# v7-flex2811_long.net
KiCad netlist of a schematic drawn in EAGLE
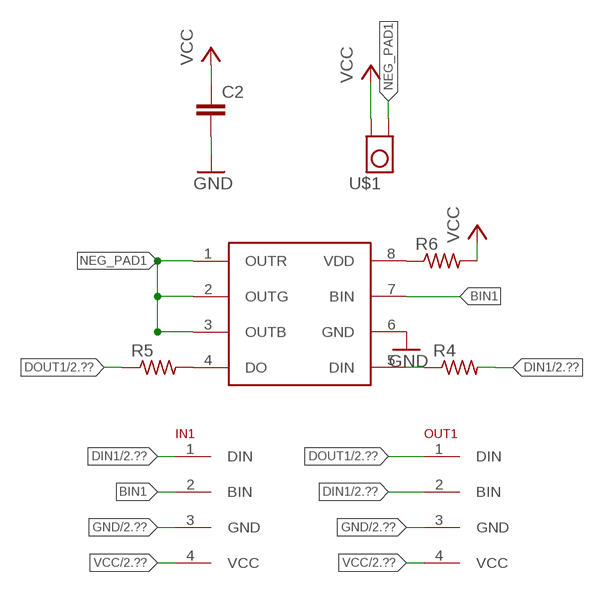
[diagram p0: schematic, sheet 1]
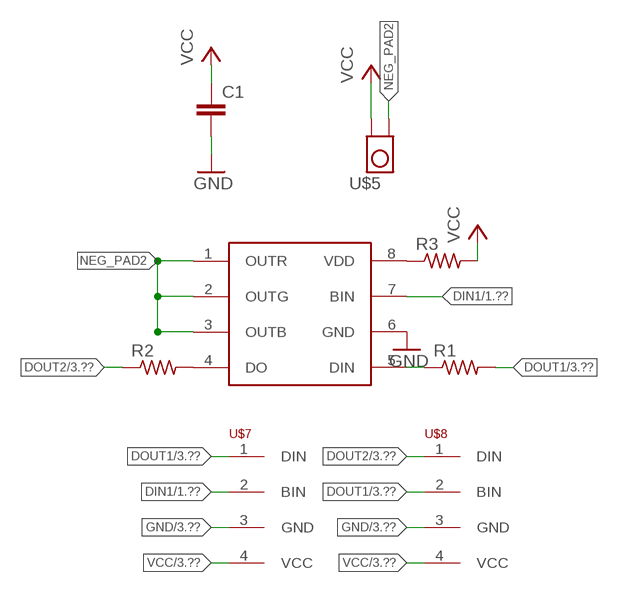
[diagram p1: schematic, sheet 2]
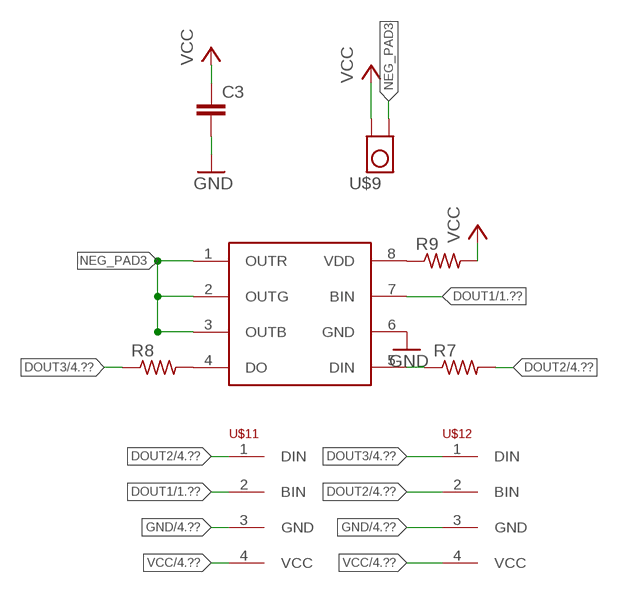
[diagram p2: schematic, sheet 3]
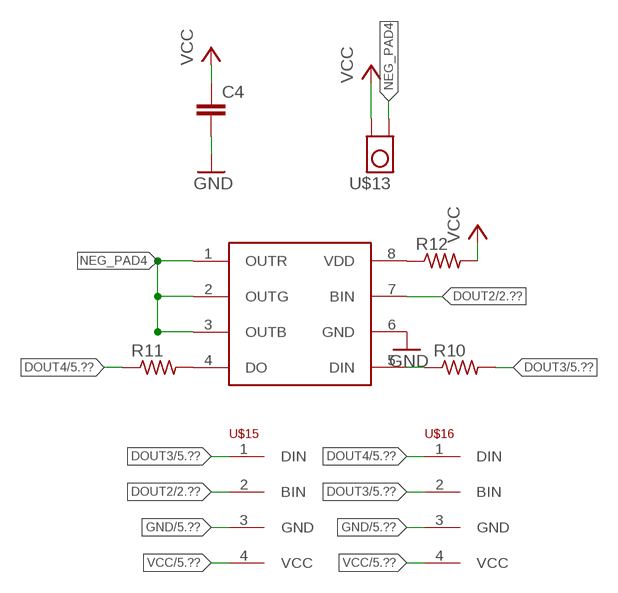
[diagram p3: schematic, sheet 4]
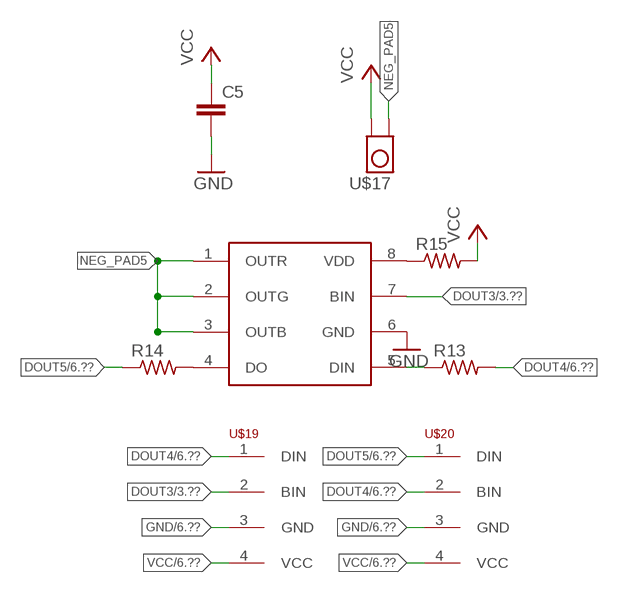
[diagram p4: schematic, sheet 5]
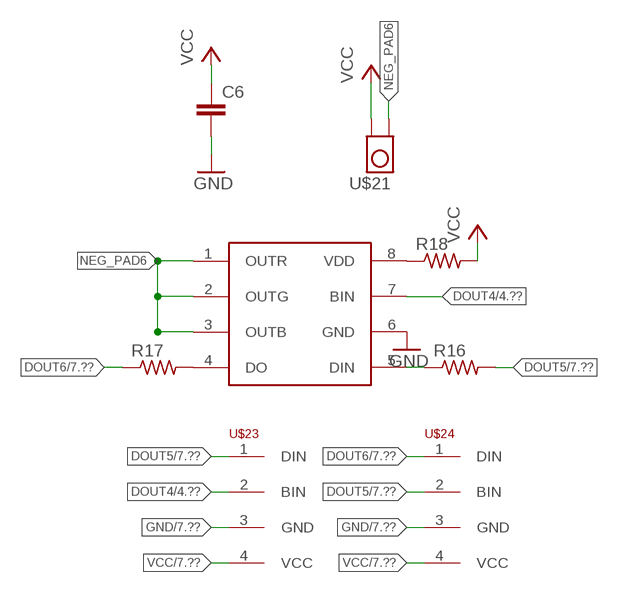
[diagram p5: schematic, sheet 6]
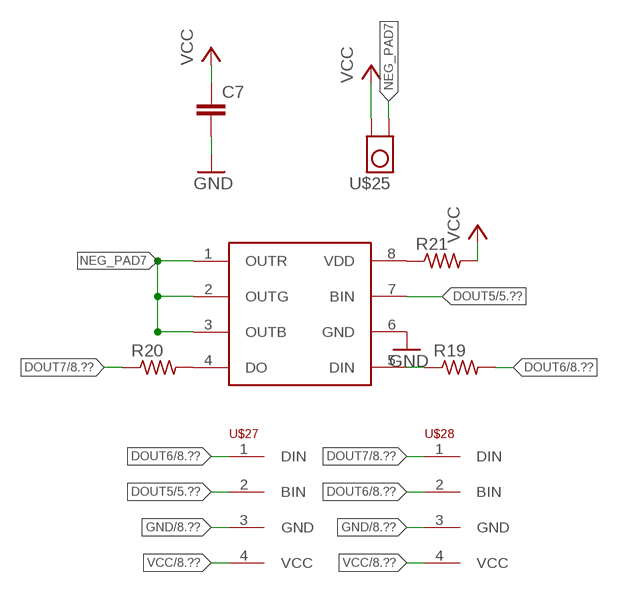
[diagram p6: schematic, sheet 7]
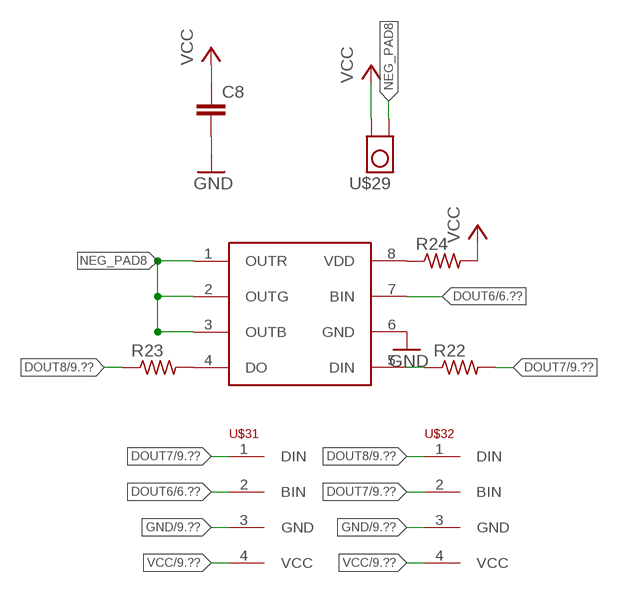
[diagram p7: schematic, sheet 8]
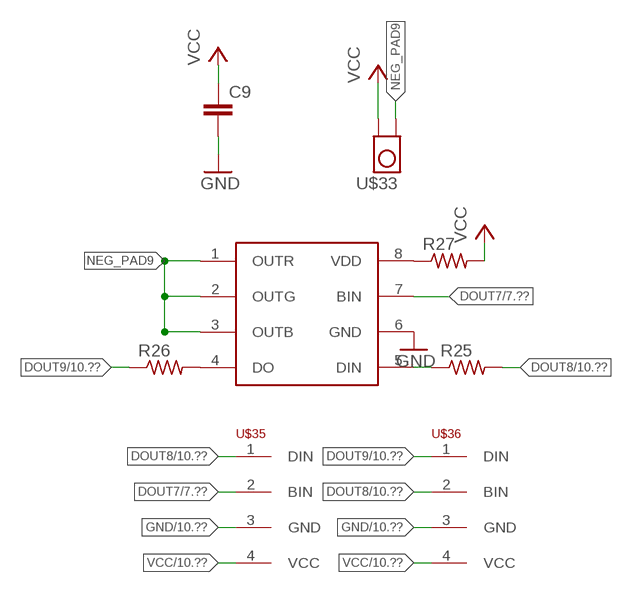
[diagram p8: schematic, sheet 9]
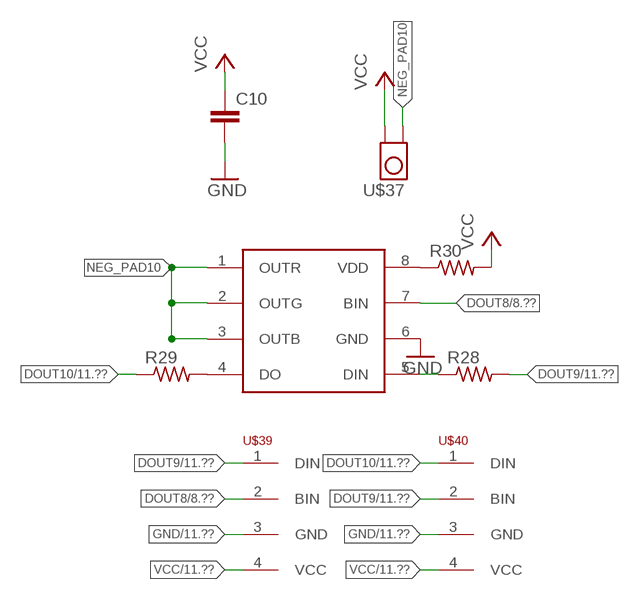
[diagram p9: schematic, sheet 10]
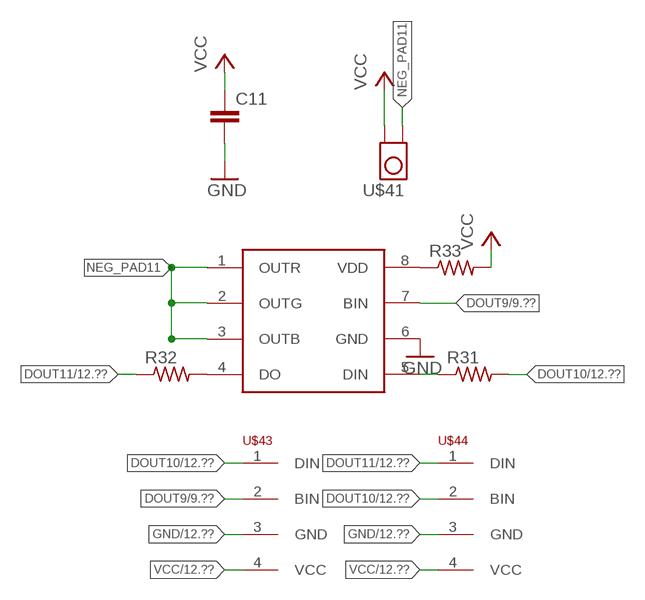
[diagram p10: schematic, sheet 11]
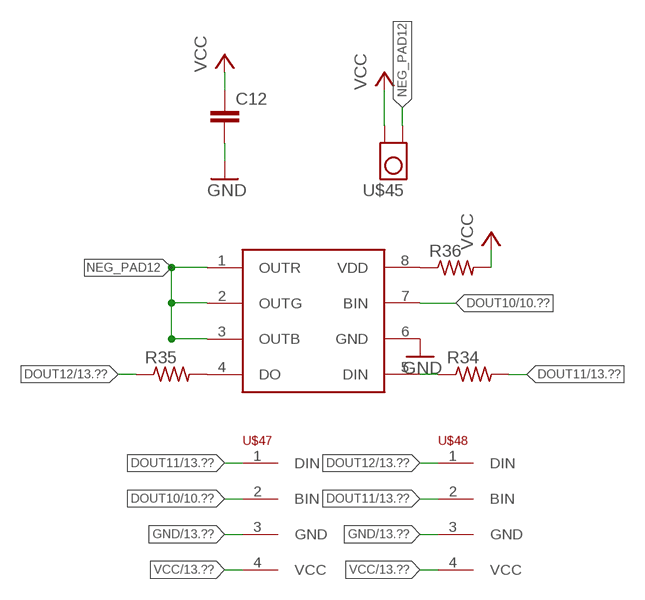
[diagram p11: schematic, sheet 12]
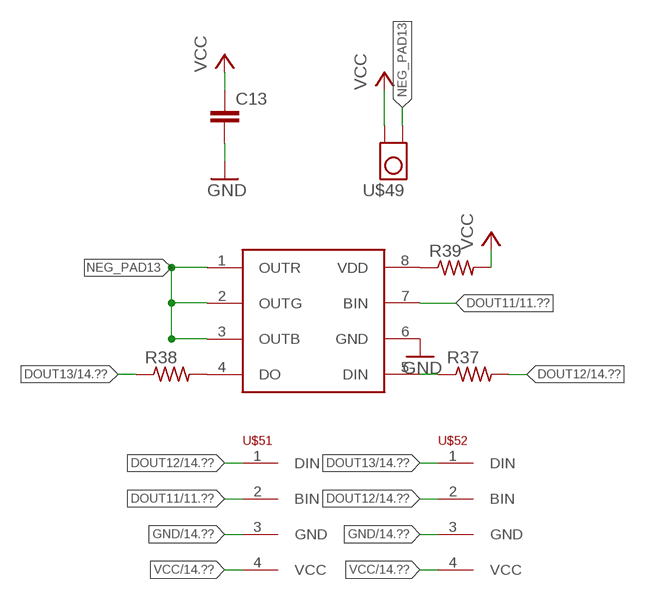
[diagram p12: schematic, sheet 13]
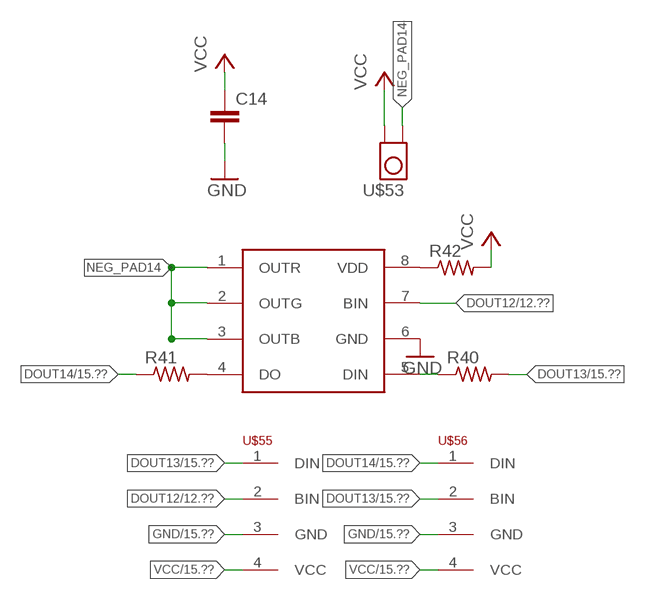
[diagram p13: schematic, sheet 14]
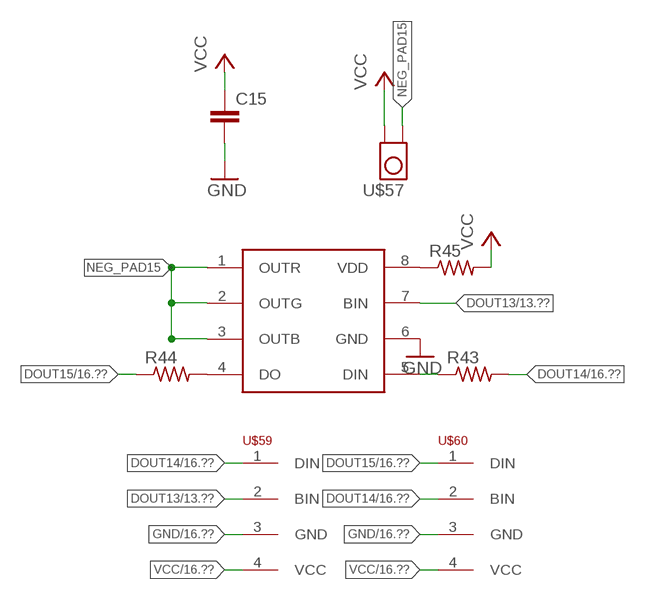
[diagram p14: schematic, sheet 15]
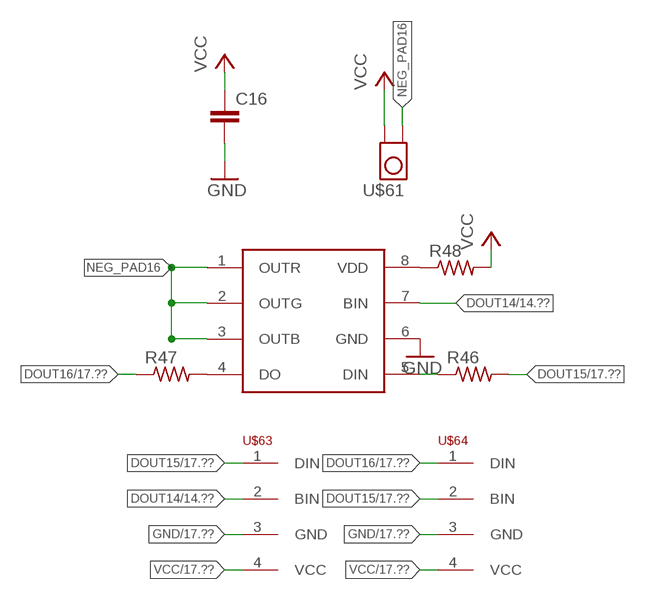
[diagram p15: schematic, sheet 16]
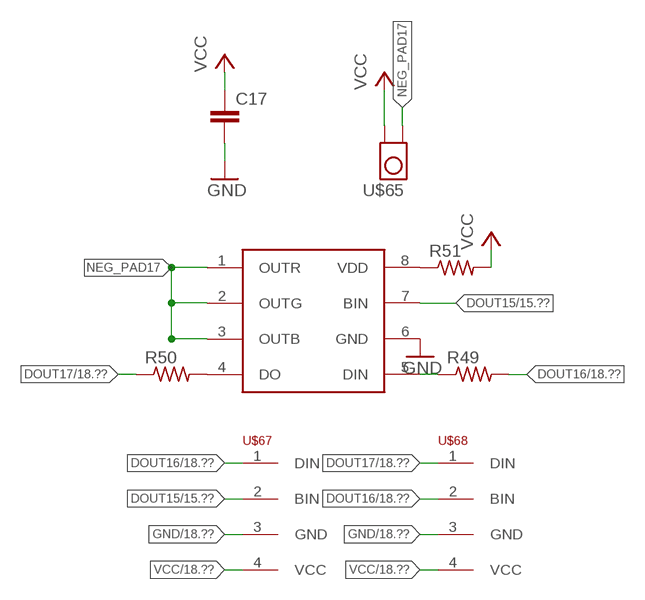
[diagram p16: schematic, sheet 17]
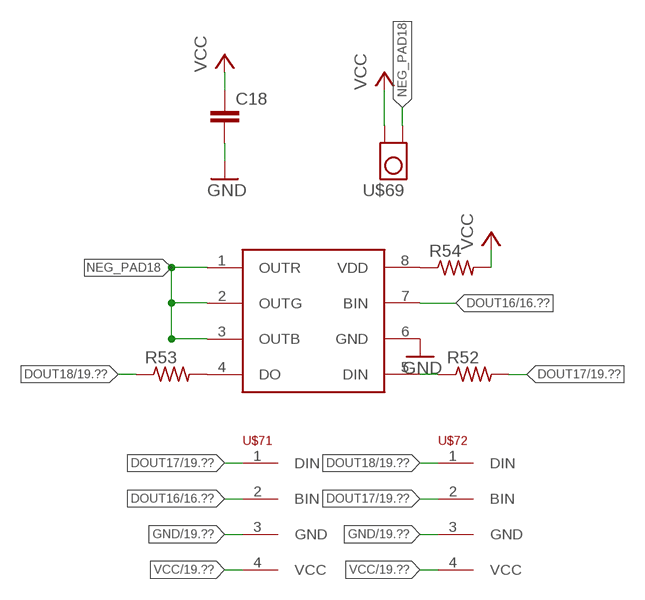
[diagram p17: schematic, sheet 18]
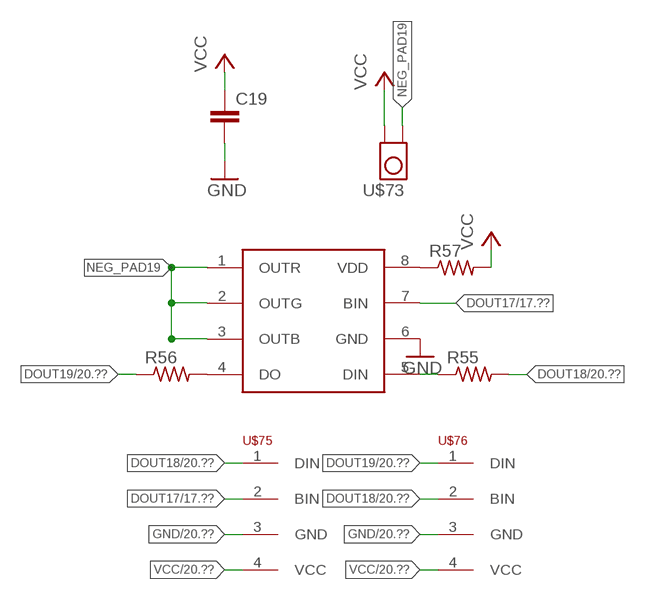
[diagram p18: schematic, sheet 19]
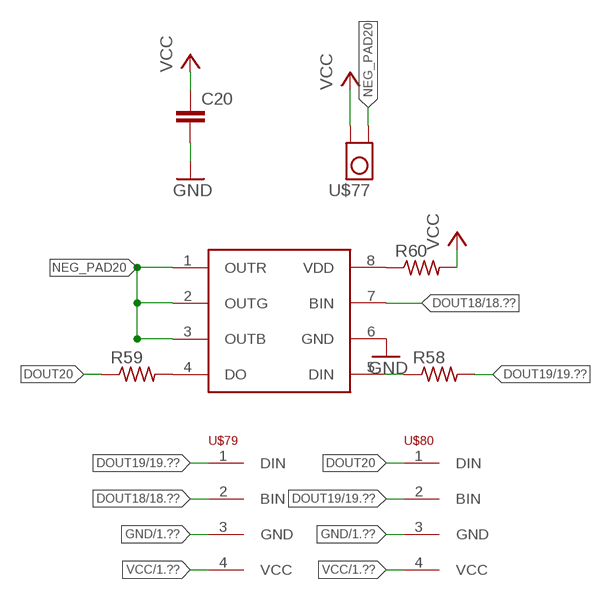
[diagram p19: schematic, sheet 20]

(export (version "E")
  (design (tool "Eeschema 10.0.6"))
  (components
    (comp (ref "C20")
      (value "C-EUC0201")
      (footprint "eagle-import:C0201")
      (libsource (lib "eagle-import") (part "C-EUC0201"))
    )
    (comp (ref "R58")
      (value "R-US_R0201")
      (footprint "eagle-import:R0201")
      (libsource (lib "eagle-import") (part "R-US_R0201"))
    )
    (comp (ref "R59")
      (value "R-US_R0201")
      (footprint "eagle-import:R0201")
      (libsource (lib "eagle-import") (part "R-US_R0201"))
    )
    (comp (ref "R60")
      (value "R-US_R0201")
      (footprint "eagle-import:R0201")
      (libsource (lib "eagle-import") (part "R-US_R0201"))
    )
    (comp (ref "U$77")
      (value "TP_4MM_MED_PAD")
      (footprint "eagle-import:TP_4MM_MED_PAD")
      (libsource (lib "eagle-import") (part "TP_4MM_MED_PAD"))
    )
    (comp (ref "U$78")
      (value "WS2818")
      (footprint "eagle-import:SO08")
      (libsource (lib "eagle-import") (part "adafruit_WS2818"))
    )
    (comp (ref "U$79")
      (value "4PAD")
      (footprint "eagle-import:4PAD")
      (libsource (lib "eagle-import") (part "4PAD"))
    )
    (comp (ref "U$80")
      (value "4PAD")
      (footprint "eagle-import:4PAD")
      (libsource (lib "eagle-import") (part "4PAD"))
    )
    (comp (ref "C16")
      (value "C-EUC0201")
      (footprint "eagle-import:C0201")
      (libsource (lib "eagle-import") (part "C-EUC0201"))
    )
    (comp (ref "R46")
      (value "R-US_R0201")
      (footprint "eagle-import:R0201")
      (libsource (lib "eagle-import") (part "R-US_R0201"))
    )
    (comp (ref "R47")
      (value "R-US_R0201")
      (footprint "eagle-import:R0201")
      (libsource (lib "eagle-import") (part "R-US_R0201"))
    )
    (comp (ref "R48")
      (value "R-US_R0201")
      (footprint "eagle-import:R0201")
      (libsource (lib "eagle-import") (part "R-US_R0201"))
    )
    (comp (ref "U$61")
      (value "TP_4MM_MED_PAD")
      (footprint "eagle-import:TP_4MM_MED_PAD")
      (libsource (lib "eagle-import") (part "TP_4MM_MED_PAD"))
    )
    (comp (ref "U$62")
      (value "WS2818")
      (footprint "eagle-import:SO08")
      (libsource (lib "eagle-import") (part "adafruit_WS2818"))
    )
    (comp (ref "U$63")
      (value "4PAD")
      (footprint "eagle-import:4PAD")
      (libsource (lib "eagle-import") (part "4PAD"))
    )
    (comp (ref "U$64")
      (value "4PAD")
      (footprint "eagle-import:4PAD")
      (libsource (lib "eagle-import") (part "4PAD"))
    )
    (comp (ref "C6")
      (value "C-EUC0201")
      (footprint "eagle-import:C0201")
      (libsource (lib "eagle-import") (part "C-EUC0201"))
    )
    (comp (ref "R16")
      (value "R-US_R0201")
      (footprint "eagle-import:R0201")
      (libsource (lib "eagle-import") (part "R-US_R0201"))
    )
    (comp (ref "R17")
      (value "R-US_R0201")
      (footprint "eagle-import:R0201")
      (libsource (lib "eagle-import") (part "R-US_R0201"))
    )
    (comp (ref "R18")
      (value "R-US_R0201")
      (footprint "eagle-import:R0201")
      (libsource (lib "eagle-import") (part "R-US_R0201"))
    )
    (comp (ref "U$21")
      (value "TP_4MM_MED_PAD")
      (footprint "eagle-import:TP_4MM_MED_PAD")
      (libsource (lib "eagle-import") (part "TP_4MM_MED_PAD"))
    )
    (comp (ref "U$22")
      (value "WS2818")
      (footprint "eagle-import:SO08")
      (libsource (lib "eagle-import") (part "adafruit_WS2818"))
    )
    (comp (ref "U$23")
      (value "4PAD")
      (footprint "eagle-import:4PAD")
      (libsource (lib "eagle-import") (part "4PAD"))
    )
    (comp (ref "U$24")
      (value "4PAD")
      (footprint "eagle-import:4PAD")
      (libsource (lib "eagle-import") (part "4PAD"))
    )
    (comp (ref "C18")
      (value "C-EUC0201")
      (footprint "eagle-import:C0201")
      (libsource (lib "eagle-import") (part "C-EUC0201"))
    )
    (comp (ref "R52")
      (value "R-US_R0201")
      (footprint "eagle-import:R0201")
      (libsource (lib "eagle-import") (part "R-US_R0201"))
    )
    (comp (ref "R53")
      (value "R-US_R0201")
      (footprint "eagle-import:R0201")
      (libsource (lib "eagle-import") (part "R-US_R0201"))
    )
    (comp (ref "R54")
      (value "R-US_R0201")
      (footprint "eagle-import:R0201")
      (libsource (lib "eagle-import") (part "R-US_R0201"))
    )
    (comp (ref "U$69")
      (value "TP_4MM_MED_PAD")
      (footprint "eagle-import:TP_4MM_MED_PAD")
      (libsource (lib "eagle-import") (part "TP_4MM_MED_PAD"))
    )
    (comp (ref "U$70")
      (value "WS2818")
      (footprint "eagle-import:SO08")
      (libsource (lib "eagle-import") (part "adafruit_WS2818"))
    )
    (comp (ref "U$71")
      (value "4PAD")
      (footprint "eagle-import:4PAD")
      (libsource (lib "eagle-import") (part "4PAD"))
    )
    (comp (ref "U$72")
      (value "4PAD")
      (footprint "eagle-import:4PAD")
      (libsource (lib "eagle-import") (part "4PAD"))
    )
    (comp (ref "C12")
      (value "C-EUC0201")
      (footprint "eagle-import:C0201")
      (libsource (lib "eagle-import") (part "C-EUC0201"))
    )
    (comp (ref "R34")
      (value "R-US_R0201")
      (footprint "eagle-import:R0201")
      (libsource (lib "eagle-import") (part "R-US_R0201"))
    )
    (comp (ref "R35")
      (value "R-US_R0201")
      (footprint "eagle-import:R0201")
      (libsource (lib "eagle-import") (part "R-US_R0201"))
    )
    (comp (ref "R36")
      (value "R-US_R0201")
      (footprint "eagle-import:R0201")
      (libsource (lib "eagle-import") (part "R-US_R0201"))
    )
    (comp (ref "U$45")
      (value "TP_4MM_MED_PAD")
      (footprint "eagle-import:TP_4MM_MED_PAD")
      (libsource (lib "eagle-import") (part "TP_4MM_MED_PAD"))
    )
    (comp (ref "U$46")
      (value "WS2818")
      (footprint "eagle-import:SO08")
      (libsource (lib "eagle-import") (part "adafruit_WS2818"))
    )
    (comp (ref "U$47")
      (value "4PAD")
      (footprint "eagle-import:4PAD")
      (libsource (lib "eagle-import") (part "4PAD"))
    )
    (comp (ref "U$48")
      (value "4PAD")
      (footprint "eagle-import:4PAD")
      (libsource (lib "eagle-import") (part "4PAD"))
    )
    (comp (ref "C11")
      (value "C-EUC0201")
      (footprint "eagle-import:C0201")
      (libsource (lib "eagle-import") (part "C-EUC0201"))
    )
    (comp (ref "R31")
      (value "R-US_R0201")
      (footprint "eagle-import:R0201")
      (libsource (lib "eagle-import") (part "R-US_R0201"))
    )
    (comp (ref "R32")
      (value "R-US_R0201")
      (footprint "eagle-import:R0201")
      (libsource (lib "eagle-import") (part "R-US_R0201"))
    )
    (comp (ref "R33")
      (value "R-US_R0201")
      (footprint "eagle-import:R0201")
      (libsource (lib "eagle-import") (part "R-US_R0201"))
    )
    (comp (ref "U$41")
      (value "TP_4MM_MED_PAD")
      (footprint "eagle-import:TP_4MM_MED_PAD")
      (libsource (lib "eagle-import") (part "TP_4MM_MED_PAD"))
    )
    (comp (ref "U$42")
      (value "WS2818")
      (footprint "eagle-import:SO08")
      (libsource (lib "eagle-import") (part "adafruit_WS2818"))
    )
    (comp (ref "U$43")
      (value "4PAD")
      (footprint "eagle-import:4PAD")
      (libsource (lib "eagle-import") (part "4PAD"))
    )
    (comp (ref "U$44")
      (value "4PAD")
      (footprint "eagle-import:4PAD")
      (libsource (lib "eagle-import") (part "4PAD"))
    )
    (comp (ref "C10")
      (value "C-EUC0201")
      (footprint "eagle-import:C0201")
      (libsource (lib "eagle-import") (part "C-EUC0201"))
    )
    (comp (ref "R28")
      (value "R-US_R0201")
      (footprint "eagle-import:R0201")
      (libsource (lib "eagle-import") (part "R-US_R0201"))
    )
    (comp (ref "R29")
      (value "R-US_R0201")
      (footprint "eagle-import:R0201")
      (libsource (lib "eagle-import") (part "R-US_R0201"))
    )
    (comp (ref "R30")
      (value "R-US_R0201")
      (footprint "eagle-import:R0201")
      (libsource (lib "eagle-import") (part "R-US_R0201"))
    )
    (comp (ref "U$37")
      (value "TP_4MM_MED_PAD")
      (footprint "eagle-import:TP_4MM_MED_PAD")
      (libsource (lib "eagle-import") (part "TP_4MM_MED_PAD"))
    )
    (comp (ref "U$38")
      (value "WS2818")
      (footprint "eagle-import:SO08")
      (libsource (lib "eagle-import") (part "adafruit_WS2818"))
    )
    (comp (ref "U$39")
      (value "4PAD")
      (footprint "eagle-import:4PAD")
      (libsource (lib "eagle-import") (part "4PAD"))
    )
    (comp (ref "U$40")
      (value "4PAD")
      (footprint "eagle-import:4PAD")
      (libsource (lib "eagle-import") (part "4PAD"))
    )
    (comp (ref "C7")
      (value "C-EUC0201")
      (footprint "eagle-import:C0201")
      (libsource (lib "eagle-import") (part "C-EUC0201"))
    )
    (comp (ref "R19")
      (value "R-US_R0201")
      (footprint "eagle-import:R0201")
      (libsource (lib "eagle-import") (part "R-US_R0201"))
    )
    (comp (ref "R20")
      (value "R-US_R0201")
      (footprint "eagle-import:R0201")
      (libsource (lib "eagle-import") (part "R-US_R0201"))
    )
    (comp (ref "R21")
      (value "R-US_R0201")
      (footprint "eagle-import:R0201")
      (libsource (lib "eagle-import") (part "R-US_R0201"))
    )
    (comp (ref "U$25")
      (value "TP_4MM_MED_PAD")
      (footprint "eagle-import:TP_4MM_MED_PAD")
      (libsource (lib "eagle-import") (part "TP_4MM_MED_PAD"))
    )
    (comp (ref "U$26")
      (value "WS2818")
      (footprint "eagle-import:SO08")
      (libsource (lib "eagle-import") (part "adafruit_WS2818"))
    )
    (comp (ref "U$27")
      (value "4PAD")
      (footprint "eagle-import:4PAD")
      (libsource (lib "eagle-import") (part "4PAD"))
    )
    (comp (ref "U$28")
      (value "4PAD")
      (footprint "eagle-import:4PAD")
      (libsource (lib "eagle-import") (part "4PAD"))
    )
    (comp (ref "C2")
      (value "C-EUC0201")
      (footprint "eagle-import:C0201")
      (libsource (lib "eagle-import") (part "C-EUC0201"))
    )
    (comp (ref "IN1")
      (value "4PAD")
      (footprint "eagle-import:4PAD")
      (libsource (lib "eagle-import") (part "4PAD"))
    )
    (comp (ref "OUT1")
      (value "4PAD")
      (footprint "eagle-import:4PAD")
      (libsource (lib "eagle-import") (part "4PAD"))
    )
    (comp (ref "R4")
      (value "R-US_R0201")
      (footprint "eagle-import:R0201")
      (libsource (lib "eagle-import") (part "R-US_R0201"))
    )
    (comp (ref "R5")
      (value "R-US_R0201")
      (footprint "eagle-import:R0201")
      (libsource (lib "eagle-import") (part "R-US_R0201"))
    )
    (comp (ref "R6")
      (value "R-US_R0201")
      (footprint "eagle-import:R0201")
      (libsource (lib "eagle-import") (part "R-US_R0201"))
    )
    (comp (ref "U$1")
      (value "TP_4MM_MED_PAD")
      (footprint "eagle-import:TP_4MM_MED_PAD")
      (libsource (lib "eagle-import") (part "TP_4MM_MED_PAD"))
    )
    (comp (ref "U$2")
      (value "WS2818")
      (footprint "eagle-import:SO08")
      (libsource (lib "eagle-import") (part "WS2818"))
    )
    (comp (ref "C4")
      (value "C-EUC0201")
      (footprint "eagle-import:C0201")
      (libsource (lib "eagle-import") (part "C-EUC0201"))
    )
    (comp (ref "R10")
      (value "R-US_R0201")
      (footprint "eagle-import:R0201")
      (libsource (lib "eagle-import") (part "R-US_R0201"))
    )
    (comp (ref "R11")
      (value "R-US_R0201")
      (footprint "eagle-import:R0201")
      (libsource (lib "eagle-import") (part "R-US_R0201"))
    )
    (comp (ref "R12")
      (value "R-US_R0201")
      (footprint "eagle-import:R0201")
      (libsource (lib "eagle-import") (part "R-US_R0201"))
    )
    (comp (ref "U$13")
      (value "TP_4MM_MED_PAD")
      (footprint "eagle-import:TP_4MM_MED_PAD")
      (libsource (lib "eagle-import") (part "TP_4MM_MED_PAD"))
    )
    (comp (ref "U$14")
      (value "WS2818")
      (footprint "eagle-import:SO08")
      (libsource (lib "eagle-import") (part "adafruit_WS2818"))
    )
    (comp (ref "U$15")
      (value "4PAD")
      (footprint "eagle-import:4PAD")
      (libsource (lib "eagle-import") (part "4PAD"))
    )
    (comp (ref "U$16")
      (value "4PAD")
      (footprint "eagle-import:4PAD")
      (libsource (lib "eagle-import") (part "4PAD"))
    )
    (comp (ref "C3")
      (value "C-EUC0201")
      (footprint "eagle-import:C0201")
      (libsource (lib "eagle-import") (part "C-EUC0201"))
    )
    (comp (ref "R7")
      (value "R-US_R0201")
      (footprint "eagle-import:R0201")
      (libsource (lib "eagle-import") (part "R-US_R0201"))
    )
    (comp (ref "R8")
      (value "R-US_R0201")
      (footprint "eagle-import:R0201")
      (libsource (lib "eagle-import") (part "R-US_R0201"))
    )
    (comp (ref "R9")
      (value "R-US_R0201")
      (footprint "eagle-import:R0201")
      (libsource (lib "eagle-import") (part "R-US_R0201"))
    )
    (comp (ref "U$9")
      (value "TP_4MM_MED_PAD")
      (footprint "eagle-import:TP_4MM_MED_PAD")
      (libsource (lib "eagle-import") (part "TP_4MM_MED_PAD"))
    )
    (comp (ref "U$10")
      (value "WS2818")
      (footprint "eagle-import:SO08")
      (libsource (lib "eagle-import") (part "adafruit_WS2818"))
    )
    (comp (ref "U$11")
      (value "4PAD")
      (footprint "eagle-import:4PAD")
      (libsource (lib "eagle-import") (part "4PAD"))
    )
    (comp (ref "U$12")
      (value "4PAD")
      (footprint "eagle-import:4PAD")
      (libsource (lib "eagle-import") (part "4PAD"))
    )
    (comp (ref "C17")
      (value "C-EUC0201")
      (footprint "eagle-import:C0201")
      (libsource (lib "eagle-import") (part "C-EUC0201"))
    )
    (comp (ref "R49")
      (value "R-US_R0201")
      (footprint "eagle-import:R0201")
      (libsource (lib "eagle-import") (part "R-US_R0201"))
    )
    (comp (ref "R50")
      (value "R-US_R0201")
      (footprint "eagle-import:R0201")
      (libsource (lib "eagle-import") (part "R-US_R0201"))
    )
    (comp (ref "R51")
      (value "R-US_R0201")
      (footprint "eagle-import:R0201")
      (libsource (lib "eagle-import") (part "R-US_R0201"))
    )
    (comp (ref "U$65")
      (value "TP_4MM_MED_PAD")
      (footprint "eagle-import:TP_4MM_MED_PAD")
      (libsource (lib "eagle-import") (part "TP_4MM_MED_PAD"))
    )
    (comp (ref "U$66")
      (value "WS2818")
      (footprint "eagle-import:SO08")
      (libsource (lib "eagle-import") (part "adafruit_WS2818"))
    )
    (comp (ref "U$67")
      (value "4PAD")
      (footprint "eagle-import:4PAD")
      (libsource (lib "eagle-import") (part "4PAD"))
    )
    (comp (ref "U$68")
      (value "4PAD")
      (footprint "eagle-import:4PAD")
      (libsource (lib "eagle-import") (part "4PAD"))
    )
    (comp (ref "C5")
      (value "C-EUC0201")
      (footprint "eagle-import:C0201")
      (libsource (lib "eagle-import") (part "C-EUC0201"))
    )
    (comp (ref "R13")
      (value "R-US_R0201")
      (footprint "eagle-import:R0201")
      (libsource (lib "eagle-import") (part "R-US_R0201"))
    )
    (comp (ref "R14")
      (value "R-US_R0201")
      (footprint "eagle-import:R0201")
      (libsource (lib "eagle-import") (part "R-US_R0201"))
    )
    (comp (ref "R15")
      (value "R-US_R0201")
      (footprint "eagle-import:R0201")
      (libsource (lib "eagle-import") (part "R-US_R0201"))
    )
    (comp (ref "U$17")
      (value "TP_4MM_MED_PAD")
      (footprint "eagle-import:TP_4MM_MED_PAD")
      (libsource (lib "eagle-import") (part "TP_4MM_MED_PAD"))
    )
    (comp (ref "U$18")
      (value "WS2818")
      (footprint "eagle-import:SO08")
      (libsource (lib "eagle-import") (part "adafruit_WS2818"))
    )
    (comp (ref "U$19")
      (value "4PAD")
      (footprint "eagle-import:4PAD")
      (libsource (lib "eagle-import") (part "4PAD"))
    )
    (comp (ref "U$20")
      (value "4PAD")
      (footprint "eagle-import:4PAD")
      (libsource (lib "eagle-import") (part "4PAD"))
    )
    (comp (ref "C14")
      (value "C-EUC0201")
      (footprint "eagle-import:C0201")
      (libsource (lib "eagle-import") (part "C-EUC0201"))
    )
    (comp (ref "R40")
      (value "R-US_R0201")
      (footprint "eagle-import:R0201")
      (libsource (lib "eagle-import") (part "R-US_R0201"))
    )
    (comp (ref "R41")
      (value "R-US_R0201")
      (footprint "eagle-import:R0201")
      (libsource (lib "eagle-import") (part "R-US_R0201"))
    )
    (comp (ref "R42")
      (value "R-US_R0201")
      (footprint "eagle-import:R0201")
      (libsource (lib "eagle-import") (part "R-US_R0201"))
    )
    (comp (ref "U$53")
      (value "TP_4MM_MED_PAD")
      (footprint "eagle-import:TP_4MM_MED_PAD")
      (libsource (lib "eagle-import") (part "TP_4MM_MED_PAD"))
    )
    (comp (ref "U$54")
      (value "WS2818")
      (footprint "eagle-import:SO08")
      (libsource (lib "eagle-import") (part "adafruit_WS2818"))
    )
    (comp (ref "U$55")
      (value "4PAD")
      (footprint "eagle-import:4PAD")
      (libsource (lib "eagle-import") (part "4PAD"))
    )
    (comp (ref "U$56")
      (value "4PAD")
      (footprint "eagle-import:4PAD")
      (libsource (lib "eagle-import") (part "4PAD"))
    )
    (comp (ref "C19")
      (value "C-EUC0201")
      (footprint "eagle-import:C0201")
      (libsource (lib "eagle-import") (part "C-EUC0201"))
    )
    (comp (ref "R55")
      (value "R-US_R0201")
      (footprint "eagle-import:R0201")
      (libsource (lib "eagle-import") (part "R-US_R0201"))
    )
    (comp (ref "R56")
      (value "R-US_R0201")
      (footprint "eagle-import:R0201")
      (libsource (lib "eagle-import") (part "R-US_R0201"))
    )
    (comp (ref "R57")
      (value "R-US_R0201")
      (footprint "eagle-import:R0201")
      (libsource (lib "eagle-import") (part "R-US_R0201"))
    )
    (comp (ref "U$73")
      (value "TP_4MM_MED_PAD")
      (footprint "eagle-import:TP_4MM_MED_PAD")
      (libsource (lib "eagle-import") (part "TP_4MM_MED_PAD"))
    )
    (comp (ref "U$74")
      (value "WS2818")
      (footprint "eagle-import:SO08")
      (libsource (lib "eagle-import") (part "adafruit_WS2818"))
    )
    (comp (ref "U$75")
      (value "4PAD")
      (footprint "eagle-import:4PAD")
      (libsource (lib "eagle-import") (part "4PAD"))
    )
    (comp (ref "U$76")
      (value "4PAD")
      (footprint "eagle-import:4PAD")
      (libsource (lib "eagle-import") (part "4PAD"))
    )
    (comp (ref "C15")
      (value "C-EUC0201")
      (footprint "eagle-import:C0201")
      (libsource (lib "eagle-import") (part "C-EUC0201"))
    )
    (comp (ref "R43")
      (value "R-US_R0201")
      (footprint "eagle-import:R0201")
      (libsource (lib "eagle-import") (part "R-US_R0201"))
    )
    (comp (ref "R44")
      (value "R-US_R0201")
      (footprint "eagle-import:R0201")
      (libsource (lib "eagle-import") (part "R-US_R0201"))
    )
    (comp (ref "R45")
      (value "R-US_R0201")
      (footprint "eagle-import:R0201")
      (libsource (lib "eagle-import") (part "R-US_R0201"))
    )
    (comp (ref "U$57")
      (value "TP_4MM_MED_PAD")
      (footprint "eagle-import:TP_4MM_MED_PAD")
      (libsource (lib "eagle-import") (part "TP_4MM_MED_PAD"))
    )
    (comp (ref "U$58")
      (value "WS2818")
      (footprint "eagle-import:SO08")
      (libsource (lib "eagle-import") (part "adafruit_WS2818"))
    )
    (comp (ref "U$59")
      (value "4PAD")
      (footprint "eagle-import:4PAD")
      (libsource (lib "eagle-import") (part "4PAD"))
    )
    (comp (ref "U$60")
      (value "4PAD")
      (footprint "eagle-import:4PAD")
      (libsource (lib "eagle-import") (part "4PAD"))
    )
    (comp (ref "C13")
      (value "C-EUC0201")
      (footprint "eagle-import:C0201")
      (libsource (lib "eagle-import") (part "C-EUC0201"))
    )
    (comp (ref "R37")
      (value "R-US_R0201")
      (footprint "eagle-import:R0201")
      (libsource (lib "eagle-import") (part "R-US_R0201"))
    )
    (comp (ref "R38")
      (value "R-US_R0201")
      (footprint "eagle-import:R0201")
      (libsource (lib "eagle-import") (part "R-US_R0201"))
    )
    (comp (ref "R39")
      (value "R-US_R0201")
      (footprint "eagle-import:R0201")
      (libsource (lib "eagle-import") (part "R-US_R0201"))
    )
    (comp (ref "U$49")
      (value "TP_4MM_MED_PAD")
      (footprint "eagle-import:TP_4MM_MED_PAD")
      (libsource (lib "eagle-import") (part "TP_4MM_MED_PAD"))
    )
    (comp (ref "U$50")
      (value "WS2818")
      (footprint "eagle-import:SO08")
      (libsource (lib "eagle-import") (part "adafruit_WS2818"))
    )
    (comp (ref "U$51")
      (value "4PAD")
      (footprint "eagle-import:4PAD")
      (libsource (lib "eagle-import") (part "4PAD"))
    )
    (comp (ref "U$52")
      (value "4PAD")
      (footprint "eagle-import:4PAD")
      (libsource (lib "eagle-import") (part "4PAD"))
    )
    (comp (ref "C9")
      (value "C-EUC0201")
      (footprint "eagle-import:C0201")
      (libsource (lib "eagle-import") (part "C-EUC0201"))
    )
    (comp (ref "R25")
      (value "R-US_R0201")
      (footprint "eagle-import:R0201")
      (libsource (lib "eagle-import") (part "R-US_R0201"))
    )
    (comp (ref "R26")
      (value "R-US_R0201")
      (footprint "eagle-import:R0201")
      (libsource (lib "eagle-import") (part "R-US_R0201"))
    )
    (comp (ref "R27")
      (value "R-US_R0201")
      (footprint "eagle-import:R0201")
      (libsource (lib "eagle-import") (part "R-US_R0201"))
    )
    (comp (ref "U$33")
      (value "TP_4MM_MED_PAD")
      (footprint "eagle-import:TP_4MM_MED_PAD")
      (libsource (lib "eagle-import") (part "TP_4MM_MED_PAD"))
    )
    (comp (ref "U$34")
      (value "WS2818")
      (footprint "eagle-import:SO08")
      (libsource (lib "eagle-import") (part "adafruit_WS2818"))
    )
    (comp (ref "U$35")
      (value "4PAD")
      (footprint "eagle-import:4PAD")
      (libsource (lib "eagle-import") (part "4PAD"))
    )
    (comp (ref "U$36")
      (value "4PAD")
      (footprint "eagle-import:4PAD")
      (libsource (lib "eagle-import") (part "4PAD"))
    )
    (comp (ref "C1")
      (value "C-EUC0201")
      (footprint "eagle-import:C0201")
      (libsource (lib "eagle-import") (part "C-EUC0201"))
    )
    (comp (ref "R1")
      (value "R-US_R0201")
      (footprint "eagle-import:R0201")
      (libsource (lib "eagle-import") (part "R-US_R0201"))
    )
    (comp (ref "R2")
      (value "R-US_R0201")
      (footprint "eagle-import:R0201")
      (libsource (lib "eagle-import") (part "R-US_R0201"))
    )
    (comp (ref "R3")
      (value "R-US_R0201")
      (footprint "eagle-import:R0201")
      (libsource (lib "eagle-import") (part "R-US_R0201"))
    )
    (comp (ref "U$5")
      (value "TP_4MM_MED_PAD")
      (footprint "eagle-import:TP_4MM_MED_PAD")
      (libsource (lib "eagle-import") (part "TP_4MM_MED_PAD"))
    )
    (comp (ref "U$6")
      (value "WS2818")
      (footprint "eagle-import:SO08")
      (libsource (lib "eagle-import") (part "adafruit_WS2818"))
    )
    (comp (ref "U$7")
      (value "4PAD")
      (footprint "eagle-import:4PAD")
      (libsource (lib "eagle-import") (part "4PAD"))
    )
    (comp (ref "U$8")
      (value "4PAD")
      (footprint "eagle-import:4PAD")
      (libsource (lib "eagle-import") (part "4PAD"))
    )
    (comp (ref "C8")
      (value "C-EUC0201")
      (footprint "eagle-import:C0201")
      (libsource (lib "eagle-import") (part "C-EUC0201"))
    )
    (comp (ref "R22")
      (value "R-US_R0201")
      (footprint "eagle-import:R0201")
      (libsource (lib "eagle-import") (part "R-US_R0201"))
    )
    (comp (ref "R23")
      (value "R-US_R0201")
      (footprint "eagle-import:R0201")
      (libsource (lib "eagle-import") (part "R-US_R0201"))
    )
    (comp (ref "R24")
      (value "R-US_R0201")
      (footprint "eagle-import:R0201")
      (libsource (lib "eagle-import") (part "R-US_R0201"))
    )
    (comp (ref "U$29")
      (value "TP_4MM_MED_PAD")
      (footprint "eagle-import:TP_4MM_MED_PAD")
      (libsource (lib "eagle-import") (part "TP_4MM_MED_PAD"))
    )
    (comp (ref "U$30")
      (value "WS2818")
      (footprint "eagle-import:SO08")
      (libsource (lib "eagle-import") (part "adafruit_WS2818"))
    )
    (comp (ref "U$31")
      (value "4PAD")
      (footprint "eagle-import:4PAD")
      (libsource (lib "eagle-import") (part "4PAD"))
    )
    (comp (ref "U$32")
      (value "4PAD")
      (footprint "eagle-import:4PAD")
      (libsource (lib "eagle-import") (part "4PAD"))
    )
  )
  (nets
    (net (code "1") (name "BIN1") (class "Default")
      (node (ref "IN1") (pin "2") (pinfunction "BIN_2") (pintype "bidirectional"))
      (node (ref "U$2") (pin "7") (pinfunction "BIN_7") (pintype "bidirectional"))
    )
    (net (code "2") (name "DIN1") (class "Default")
      (node (ref "IN1") (pin "1") (pinfunction "DIN_1") (pintype "bidirectional"))
      (node (ref "OUT1") (pin "2") (pinfunction "BIN_2") (pintype "bidirectional"))
      (node (ref "R4") (pin "2") (pinfunction "2_2") (pintype "passive"))
      (node (ref "U$6") (pin "7") (pinfunction "BIN_7") (pintype "bidirectional"))
      (node (ref "U$7") (pin "2") (pinfunction "BIN_2") (pintype "bidirectional"))
    )
    (net (code "3") (name "DOUT1") (class "Default")
      (node (ref "OUT1") (pin "1") (pinfunction "DIN_1") (pintype "bidirectional"))
      (node (ref "R1") (pin "2") (pinfunction "2_2") (pintype "passive"))
      (node (ref "R5") (pin "1") (pinfunction "1_1") (pintype "passive"))
      (node (ref "U$10") (pin "7") (pinfunction "BIN_7") (pintype "bidirectional"))
      (node (ref "U$11") (pin "2") (pinfunction "BIN_2") (pintype "bidirectional"))
      (node (ref "U$7") (pin "1") (pinfunction "DIN_1") (pintype "bidirectional"))
      (node (ref "U$8") (pin "2") (pinfunction "BIN_2") (pintype "bidirectional"))
    )
    (net (code "4") (name "DOUT2") (class "Default")
      (node (ref "R2") (pin "1") (pinfunction "1_1") (pintype "passive"))
      (node (ref "R7") (pin "2") (pinfunction "2_2") (pintype "passive"))
      (node (ref "U$11") (pin "1") (pinfunction "DIN_1") (pintype "bidirectional"))
      (node (ref "U$12") (pin "2") (pinfunction "BIN_2") (pintype "bidirectional"))
      (node (ref "U$14") (pin "7") (pinfunction "BIN_7") (pintype "bidirectional"))
      (node (ref "U$15") (pin "2") (pinfunction "BIN_2") (pintype "bidirectional"))
      (node (ref "U$8") (pin "1") (pinfunction "DIN_1") (pintype "bidirectional"))
    )
    (net (code "5") (name "DOUT3") (class "Default")
      (node (ref "R10") (pin "2") (pinfunction "2_2") (pintype "passive"))
      (node (ref "R8") (pin "1") (pinfunction "1_1") (pintype "passive"))
      (node (ref "U$12") (pin "1") (pinfunction "DIN_1") (pintype "bidirectional"))
      (node (ref "U$15") (pin "1") (pinfunction "DIN_1") (pintype "bidirectional"))
      (node (ref "U$16") (pin "2") (pinfunction "BIN_2") (pintype "bidirectional"))
      (node (ref "U$18") (pin "7") (pinfunction "BIN_7") (pintype "bidirectional"))
      (node (ref "U$19") (pin "2") (pinfunction "BIN_2") (pintype "bidirectional"))
    )
    (net (code "6") (name "DOUT4") (class "Default")
      (node (ref "R11") (pin "1") (pinfunction "1_1") (pintype "passive"))
      (node (ref "R13") (pin "2") (pinfunction "2_2") (pintype "passive"))
      (node (ref "U$16") (pin "1") (pinfunction "DIN_1") (pintype "bidirectional"))
      (node (ref "U$19") (pin "1") (pinfunction "DIN_1") (pintype "bidirectional"))
      (node (ref "U$20") (pin "2") (pinfunction "BIN_2") (pintype "bidirectional"))
      (node (ref "U$22") (pin "7") (pinfunction "BIN_7") (pintype "bidirectional"))
      (node (ref "U$23") (pin "2") (pinfunction "BIN_2") (pintype "bidirectional"))
    )
    (net (code "7") (name "DOUT5") (class "Default")
      (node (ref "R14") (pin "1") (pinfunction "1_1") (pintype "passive"))
      (node (ref "R16") (pin "2") (pinfunction "2_2") (pintype "passive"))
      (node (ref "U$20") (pin "1") (pinfunction "DIN_1") (pintype "bidirectional"))
      (node (ref "U$23") (pin "1") (pinfunction "DIN_1") (pintype "bidirectional"))
      (node (ref "U$24") (pin "2") (pinfunction "BIN_2") (pintype "bidirectional"))
      (node (ref "U$26") (pin "7") (pinfunction "BIN_7") (pintype "bidirectional"))
      (node (ref "U$27") (pin "2") (pinfunction "BIN_2") (pintype "bidirectional"))
    )
    (net (code "8") (name "DOUT6") (class "Default")
      (node (ref "R17") (pin "1") (pinfunction "1_1") (pintype "passive"))
      (node (ref "R19") (pin "2") (pinfunction "2_2") (pintype "passive"))
      (node (ref "U$24") (pin "1") (pinfunction "DIN_1") (pintype "bidirectional"))
      (node (ref "U$27") (pin "1") (pinfunction "DIN_1") (pintype "bidirectional"))
      (node (ref "U$28") (pin "2") (pinfunction "BIN_2") (pintype "bidirectional"))
      (node (ref "U$30") (pin "7") (pinfunction "BIN_7") (pintype "bidirectional"))
      (node (ref "U$31") (pin "2") (pinfunction "BIN_2") (pintype "bidirectional"))
    )
    (net (code "9") (name "DOUT7") (class "Default")
      (node (ref "R20") (pin "1") (pinfunction "1_1") (pintype "passive"))
      (node (ref "R22") (pin "2") (pinfunction "2_2") (pintype "passive"))
      (node (ref "U$28") (pin "1") (pinfunction "DIN_1") (pintype "bidirectional"))
      (node (ref "U$31") (pin "1") (pinfunction "DIN_1") (pintype "bidirectional"))
      (node (ref "U$32") (pin "2") (pinfunction "BIN_2") (pintype "bidirectional"))
      (node (ref "U$34") (pin "7") (pinfunction "BIN_7") (pintype "bidirectional"))
      (node (ref "U$35") (pin "2") (pinfunction "BIN_2") (pintype "bidirectional"))
    )
    (net (code "10") (name "DOUT8") (class "Default")
      (node (ref "R23") (pin "1") (pinfunction "1_1") (pintype "passive"))
      (node (ref "R25") (pin "2") (pinfunction "2_2") (pintype "passive"))
      (node (ref "U$32") (pin "1") (pinfunction "DIN_1") (pintype "bidirectional"))
      (node (ref "U$35") (pin "1") (pinfunction "DIN_1") (pintype "bidirectional"))
      (node (ref "U$36") (pin "2") (pinfunction "BIN_2") (pintype "bidirectional"))
      (node (ref "U$38") (pin "7") (pinfunction "BIN_7") (pintype "bidirectional"))
      (node (ref "U$39") (pin "2") (pinfunction "BIN_2") (pintype "bidirectional"))
    )
    (net (code "11") (name "DOUT9") (class "Default")
      (node (ref "R26") (pin "1") (pinfunction "1_1") (pintype "passive"))
      (node (ref "R28") (pin "2") (pinfunction "2_2") (pintype "passive"))
      (node (ref "U$36") (pin "1") (pinfunction "DIN_1") (pintype "bidirectional"))
      (node (ref "U$39") (pin "1") (pinfunction "DIN_1") (pintype "bidirectional"))
      (node (ref "U$40") (pin "2") (pinfunction "BIN_2") (pintype "bidirectional"))
      (node (ref "U$42") (pin "7") (pinfunction "BIN_7") (pintype "bidirectional"))
      (node (ref "U$43") (pin "2") (pinfunction "BIN_2") (pintype "bidirectional"))
    )
    (net (code "12") (name "DOUT10") (class "Default")
      (node (ref "R29") (pin "1") (pinfunction "1_1") (pintype "passive"))
      (node (ref "R31") (pin "2") (pinfunction "2_2") (pintype "passive"))
      (node (ref "U$40") (pin "1") (pinfunction "DIN_1") (pintype "bidirectional"))
      (node (ref "U$43") (pin "1") (pinfunction "DIN_1") (pintype "bidirectional"))
      (node (ref "U$44") (pin "2") (pinfunction "BIN_2") (pintype "bidirectional"))
      (node (ref "U$46") (pin "7") (pinfunction "BIN_7") (pintype "bidirectional"))
      (node (ref "U$47") (pin "2") (pinfunction "BIN_2") (pintype "bidirectional"))
    )
    (net (code "13") (name "DOUT11") (class "Default")
      (node (ref "R32") (pin "1") (pinfunction "1_1") (pintype "passive"))
      (node (ref "R34") (pin "2") (pinfunction "2_2") (pintype "passive"))
      (node (ref "U$44") (pin "1") (pinfunction "DIN_1") (pintype "bidirectional"))
      (node (ref "U$47") (pin "1") (pinfunction "DIN_1") (pintype "bidirectional"))
      (node (ref "U$48") (pin "2") (pinfunction "BIN_2") (pintype "bidirectional"))
      (node (ref "U$50") (pin "7") (pinfunction "BIN_7") (pintype "bidirectional"))
      (node (ref "U$51") (pin "2") (pinfunction "BIN_2") (pintype "bidirectional"))
    )
    (net (code "14") (name "DOUT12") (class "Default")
      (node (ref "R35") (pin "1") (pinfunction "1_1") (pintype "passive"))
      (node (ref "R37") (pin "2") (pinfunction "2_2") (pintype "passive"))
      (node (ref "U$48") (pin "1") (pinfunction "DIN_1") (pintype "bidirectional"))
      (node (ref "U$51") (pin "1") (pinfunction "DIN_1") (pintype "bidirectional"))
      (node (ref "U$52") (pin "2") (pinfunction "BIN_2") (pintype "bidirectional"))
      (node (ref "U$54") (pin "7") (pinfunction "BIN_7") (pintype "bidirectional"))
      (node (ref "U$55") (pin "2") (pinfunction "BIN_2") (pintype "bidirectional"))
    )
    (net (code "15") (name "DOUT13") (class "Default")
      (node (ref "R38") (pin "1") (pinfunction "1_1") (pintype "passive"))
      (node (ref "R40") (pin "2") (pinfunction "2_2") (pintype "passive"))
      (node (ref "U$52") (pin "1") (pinfunction "DIN_1") (pintype "bidirectional"))
      (node (ref "U$55") (pin "1") (pinfunction "DIN_1") (pintype "bidirectional"))
      (node (ref "U$56") (pin "2") (pinfunction "BIN_2") (pintype "bidirectional"))
      (node (ref "U$58") (pin "7") (pinfunction "BIN_7") (pintype "bidirectional"))
      (node (ref "U$59") (pin "2") (pinfunction "BIN_2") (pintype "bidirectional"))
    )
    (net (code "16") (name "DOUT14") (class "Default")
      (node (ref "R41") (pin "1") (pinfunction "1_1") (pintype "passive"))
      (node (ref "R43") (pin "2") (pinfunction "2_2") (pintype "passive"))
      (node (ref "U$56") (pin "1") (pinfunction "DIN_1") (pintype "bidirectional"))
      (node (ref "U$59") (pin "1") (pinfunction "DIN_1") (pintype "bidirectional"))
      (node (ref "U$60") (pin "2") (pinfunction "BIN_2") (pintype "bidirectional"))
      (node (ref "U$62") (pin "7") (pinfunction "BIN_7") (pintype "bidirectional"))
      (node (ref "U$63") (pin "2") (pinfunction "BIN_2") (pintype "bidirectional"))
    )
    (net (code "17") (name "DOUT15") (class "Default")
      (node (ref "R44") (pin "1") (pinfunction "1_1") (pintype "passive"))
      (node (ref "R46") (pin "2") (pinfunction "2_2") (pintype "passive"))
      (node (ref "U$60") (pin "1") (pinfunction "DIN_1") (pintype "bidirectional"))
      (node (ref "U$63") (pin "1") (pinfunction "DIN_1") (pintype "bidirectional"))
      (node (ref "U$64") (pin "2") (pinfunction "BIN_2") (pintype "bidirectional"))
      (node (ref "U$66") (pin "7") (pinfunction "BIN_7") (pintype "bidirectional"))
      (node (ref "U$67") (pin "2") (pinfunction "BIN_2") (pintype "bidirectional"))
    )
    (net (code "18") (name "DOUT16") (class "Default")
      (node (ref "R47") (pin "1") (pinfunction "1_1") (pintype "passive"))
      (node (ref "R49") (pin "2") (pinfunction "2_2") (pintype "passive"))
      (node (ref "U$64") (pin "1") (pinfunction "DIN_1") (pintype "bidirectional"))
      (node (ref "U$67") (pin "1") (pinfunction "DIN_1") (pintype "bidirectional"))
      (node (ref "U$68") (pin "2") (pinfunction "BIN_2") (pintype "bidirectional"))
      (node (ref "U$70") (pin "7") (pinfunction "BIN_7") (pintype "bidirectional"))
      (node (ref "U$71") (pin "2") (pinfunction "BIN_2") (pintype "bidirectional"))
    )
    (net (code "19") (name "DOUT17") (class "Default")
      (node (ref "R50") (pin "1") (pinfunction "1_1") (pintype "passive"))
      (node (ref "R52") (pin "2") (pinfunction "2_2") (pintype "passive"))
      (node (ref "U$68") (pin "1") (pinfunction "DIN_1") (pintype "bidirectional"))
      (node (ref "U$71") (pin "1") (pinfunction "DIN_1") (pintype "bidirectional"))
      (node (ref "U$72") (pin "2") (pinfunction "BIN_2") (pintype "bidirectional"))
      (node (ref "U$74") (pin "7") (pinfunction "BIN_7") (pintype "bidirectional"))
      (node (ref "U$75") (pin "2") (pinfunction "BIN_2") (pintype "bidirectional"))
    )
    (net (code "20") (name "DOUT18") (class "Default")
      (node (ref "R53") (pin "1") (pinfunction "1_1") (pintype "passive"))
      (node (ref "R55") (pin "2") (pinfunction "2_2") (pintype "passive"))
      (node (ref "U$72") (pin "1") (pinfunction "DIN_1") (pintype "bidirectional"))
      (node (ref "U$75") (pin "1") (pinfunction "DIN_1") (pintype "bidirectional"))
      (node (ref "U$76") (pin "2") (pinfunction "BIN_2") (pintype "bidirectional"))
      (node (ref "U$78") (pin "7") (pinfunction "BIN_7") (pintype "bidirectional"))
      (node (ref "U$79") (pin "2") (pinfunction "BIN_2") (pintype "bidirectional"))
    )
    (net (code "21") (name "DOUT19") (class "Default")
      (node (ref "R56") (pin "1") (pinfunction "1_1") (pintype "passive"))
      (node (ref "R58") (pin "2") (pinfunction "2_2") (pintype "passive"))
      (node (ref "U$76") (pin "1") (pinfunction "DIN_1") (pintype "bidirectional"))
      (node (ref "U$79") (pin "1") (pinfunction "DIN_1") (pintype "bidirectional"))
      (node (ref "U$80") (pin "2") (pinfunction "BIN_2") (pintype "bidirectional"))
    )
    (net (code "22") (name "DOUT20") (class "Default")
      (node (ref "R59") (pin "1") (pinfunction "1_1") (pintype "passive"))
      (node (ref "U$80") (pin "1") (pinfunction "DIN_1") (pintype "bidirectional"))
    )
    (net (code "23") (name "GND") (class "Default")
      (node (ref "C1") (pin "2") (pinfunction "2_2") (pintype "passive"))
      (node (ref "C10") (pin "2") (pinfunction "2_2") (pintype "passive"))
      (node (ref "C11") (pin "2") (pinfunction "2_2") (pintype "passive"))
      (node (ref "C12") (pin "2") (pinfunction "2_2") (pintype "passive"))
      (node (ref "C13") (pin "2") (pinfunction "2_2") (pintype "passive"))
      (node (ref "C14") (pin "2") (pinfunction "2_2") (pintype "passive"))
      (node (ref "C15") (pin "2") (pinfunction "2_2") (pintype "passive"))
      (node (ref "C16") (pin "2") (pinfunction "2_2") (pintype "passive"))
      (node (ref "C17") (pin "2") (pinfunction "2_2") (pintype "passive"))
      (node (ref "C18") (pin "2") (pinfunction "2_2") (pintype "passive"))
      (node (ref "C19") (pin "2") (pinfunction "2_2") (pintype "passive"))
      (node (ref "C2") (pin "2") (pinfunction "2_2") (pintype "passive"))
      (node (ref "C20") (pin "2") (pinfunction "2_2") (pintype "passive"))
      (node (ref "C3") (pin "2") (pinfunction "2_2") (pintype "passive"))
      (node (ref "C4") (pin "2") (pinfunction "2_2") (pintype "passive"))
      (node (ref "C5") (pin "2") (pinfunction "2_2") (pintype "passive"))
      (node (ref "C6") (pin "2") (pinfunction "2_2") (pintype "passive"))
      (node (ref "C7") (pin "2") (pinfunction "2_2") (pintype "passive"))
      (node (ref "C8") (pin "2") (pinfunction "2_2") (pintype "passive"))
      (node (ref "C9") (pin "2") (pinfunction "2_2") (pintype "passive"))
      (node (ref "IN1") (pin "3") (pinfunction "GND_3") (pintype "bidirectional"))
      (node (ref "OUT1") (pin "3") (pinfunction "GND_3") (pintype "bidirectional"))
      (node (ref "U$10") (pin "6") (pinfunction "GND_6") (pintype "bidirectional"))
      (node (ref "U$11") (pin "3") (pinfunction "GND_3") (pintype "bidirectional"))
      (node (ref "U$12") (pin "3") (pinfunction "GND_3") (pintype "bidirectional"))
      (node (ref "U$14") (pin "6") (pinfunction "GND_6") (pintype "bidirectional"))
      (node (ref "U$15") (pin "3") (pinfunction "GND_3") (pintype "bidirectional"))
      (node (ref "U$16") (pin "3") (pinfunction "GND_3") (pintype "bidirectional"))
      (node (ref "U$18") (pin "6") (pinfunction "GND_6") (pintype "bidirectional"))
      (node (ref "U$19") (pin "3") (pinfunction "GND_3") (pintype "bidirectional"))
      (node (ref "U$2") (pin "6") (pinfunction "GND_6") (pintype "bidirectional"))
      (node (ref "U$20") (pin "3") (pinfunction "GND_3") (pintype "bidirectional"))
      (node (ref "U$22") (pin "6") (pinfunction "GND_6") (pintype "bidirectional"))
      (node (ref "U$23") (pin "3") (pinfunction "GND_3") (pintype "bidirectional"))
      (node (ref "U$24") (pin "3") (pinfunction "GND_3") (pintype "bidirectional"))
      (node (ref "U$26") (pin "6") (pinfunction "GND_6") (pintype "bidirectional"))
      (node (ref "U$27") (pin "3") (pinfunction "GND_3") (pintype "bidirectional"))
      (node (ref "U$28") (pin "3") (pinfunction "GND_3") (pintype "bidirectional"))
      (node (ref "U$30") (pin "6") (pinfunction "GND_6") (pintype "bidirectional"))
      (node (ref "U$31") (pin "3") (pinfunction "GND_3") (pintype "bidirectional"))
      (node (ref "U$32") (pin "3") (pinfunction "GND_3") (pintype "bidirectional"))
      (node (ref "U$34") (pin "6") (pinfunction "GND_6") (pintype "bidirectional"))
      (node (ref "U$35") (pin "3") (pinfunction "GND_3") (pintype "bidirectional"))
      (node (ref "U$36") (pin "3") (pinfunction "GND_3") (pintype "bidirectional"))
      (node (ref "U$38") (pin "6") (pinfunction "GND_6") (pintype "bidirectional"))
      (node (ref "U$39") (pin "3") (pinfunction "GND_3") (pintype "bidirectional"))
      (node (ref "U$40") (pin "3") (pinfunction "GND_3") (pintype "bidirectional"))
      (node (ref "U$42") (pin "6") (pinfunction "GND_6") (pintype "bidirectional"))
      (node (ref "U$43") (pin "3") (pinfunction "GND_3") (pintype "bidirectional"))
      (node (ref "U$44") (pin "3") (pinfunction "GND_3") (pintype "bidirectional"))
      (node (ref "U$46") (pin "6") (pinfunction "GND_6") (pintype "bidirectional"))
      (node (ref "U$47") (pin "3") (pinfunction "GND_3") (pintype "bidirectional"))
      (node (ref "U$48") (pin "3") (pinfunction "GND_3") (pintype "bidirectional"))
      (node (ref "U$50") (pin "6") (pinfunction "GND_6") (pintype "bidirectional"))
      (node (ref "U$51") (pin "3") (pinfunction "GND_3") (pintype "bidirectional"))
      (node (ref "U$52") (pin "3") (pinfunction "GND_3") (pintype "bidirectional"))
      (node (ref "U$54") (pin "6") (pinfunction "GND_6") (pintype "bidirectional"))
      (node (ref "U$55") (pin "3") (pinfunction "GND_3") (pintype "bidirectional"))
      (node (ref "U$56") (pin "3") (pinfunction "GND_3") (pintype "bidirectional"))
      (node (ref "U$58") (pin "6") (pinfunction "GND_6") (pintype "bidirectional"))
      (node (ref "U$59") (pin "3") (pinfunction "GND_3") (pintype "bidirectional"))
      (node (ref "U$6") (pin "6") (pinfunction "GND_6") (pintype "bidirectional"))
      (node (ref "U$60") (pin "3") (pinfunction "GND_3") (pintype "bidirectional"))
      (node (ref "U$62") (pin "6") (pinfunction "GND_6") (pintype "bidirectional"))
      (node (ref "U$63") (pin "3") (pinfunction "GND_3") (pintype "bidirectional"))
      (node (ref "U$64") (pin "3") (pinfunction "GND_3") (pintype "bidirectional"))
      (node (ref "U$66") (pin "6") (pinfunction "GND_6") (pintype "bidirectional"))
      (node (ref "U$67") (pin "3") (pinfunction "GND_3") (pintype "bidirectional"))
      (node (ref "U$68") (pin "3") (pinfunction "GND_3") (pintype "bidirectional"))
      (node (ref "U$7") (pin "3") (pinfunction "GND_3") (pintype "bidirectional"))
      (node (ref "U$70") (pin "6") (pinfunction "GND_6") (pintype "bidirectional"))
      (node (ref "U$71") (pin "3") (pinfunction "GND_3") (pintype "bidirectional"))
      (node (ref "U$72") (pin "3") (pinfunction "GND_3") (pintype "bidirectional"))
      (node (ref "U$74") (pin "6") (pinfunction "GND_6") (pintype "bidirectional"))
      (node (ref "U$75") (pin "3") (pinfunction "GND_3") (pintype "bidirectional"))
      (node (ref "U$76") (pin "3") (pinfunction "GND_3") (pintype "bidirectional"))
      (node (ref "U$78") (pin "6") (pinfunction "GND_6") (pintype "bidirectional"))
      (node (ref "U$79") (pin "3") (pinfunction "GND_3") (pintype "bidirectional"))
      (node (ref "U$8") (pin "3") (pinfunction "GND_3") (pintype "bidirectional"))
      (node (ref "U$80") (pin "3") (pinfunction "GND_3") (pintype "bidirectional"))
    )
    (net (code "24") (name "NEG_PAD1") (class "Default")
      (node (ref "U$1") (pin "P$1") (pinfunction "0_P$1") (pintype "bidirectional"))
      (node (ref "U$2") (pin "1") (pinfunction "OUTR_1") (pintype "bidirectional"))
      (node (ref "U$2") (pin "2") (pinfunction "OUTG_2") (pintype "bidirectional"))
      (node (ref "U$2") (pin "3") (pinfunction "OUTB_3") (pintype "bidirectional"))
    )
    (net (code "25") (name "NEG_PAD2") (class "Default")
      (node (ref "U$5") (pin "P$1") (pinfunction "0_P$1") (pintype "bidirectional"))
      (node (ref "U$6") (pin "1") (pinfunction "OUTR_1") (pintype "bidirectional"))
      (node (ref "U$6") (pin "2") (pinfunction "OUTG_2") (pintype "bidirectional"))
      (node (ref "U$6") (pin "3") (pinfunction "OUTB_3") (pintype "bidirectional"))
    )
    (net (code "26") (name "NEG_PAD3") (class "Default")
      (node (ref "U$10") (pin "1") (pinfunction "OUTR_1") (pintype "bidirectional"))
      (node (ref "U$10") (pin "2") (pinfunction "OUTG_2") (pintype "bidirectional"))
      (node (ref "U$10") (pin "3") (pinfunction "OUTB_3") (pintype "bidirectional"))
      (node (ref "U$9") (pin "P$1") (pinfunction "0_P$1") (pintype "bidirectional"))
    )
    (net (code "27") (name "NEG_PAD4") (class "Default")
      (node (ref "U$13") (pin "P$1") (pinfunction "0_P$1") (pintype "bidirectional"))
      (node (ref "U$14") (pin "1") (pinfunction "OUTR_1") (pintype "bidirectional"))
      (node (ref "U$14") (pin "2") (pinfunction "OUTG_2") (pintype "bidirectional"))
      (node (ref "U$14") (pin "3") (pinfunction "OUTB_3") (pintype "bidirectional"))
    )
    (net (code "28") (name "NEG_PAD5") (class "Default")
      (node (ref "U$17") (pin "P$1") (pinfunction "0_P$1") (pintype "bidirectional"))
      (node (ref "U$18") (pin "1") (pinfunction "OUTR_1") (pintype "bidirectional"))
      (node (ref "U$18") (pin "2") (pinfunction "OUTG_2") (pintype "bidirectional"))
      (node (ref "U$18") (pin "3") (pinfunction "OUTB_3") (pintype "bidirectional"))
    )
    (net (code "29") (name "NEG_PAD6") (class "Default")
      (node (ref "U$21") (pin "P$1") (pinfunction "0_P$1") (pintype "bidirectional"))
      (node (ref "U$22") (pin "1") (pinfunction "OUTR_1") (pintype "bidirectional"))
      (node (ref "U$22") (pin "2") (pinfunction "OUTG_2") (pintype "bidirectional"))
      (node (ref "U$22") (pin "3") (pinfunction "OUTB_3") (pintype "bidirectional"))
    )
    (net (code "30") (name "NEG_PAD7") (class "Default")
      (node (ref "U$25") (pin "P$1") (pinfunction "0_P$1") (pintype "bidirectional"))
      (node (ref "U$26") (pin "1") (pinfunction "OUTR_1") (pintype "bidirectional"))
      (node (ref "U$26") (pin "2") (pinfunction "OUTG_2") (pintype "bidirectional"))
      (node (ref "U$26") (pin "3") (pinfunction "OUTB_3") (pintype "bidirectional"))
    )
    (net (code "31") (name "NEG_PAD8") (class "Default")
      (node (ref "U$29") (pin "P$1") (pinfunction "0_P$1") (pintype "bidirectional"))
      (node (ref "U$30") (pin "1") (pinfunction "OUTR_1") (pintype "bidirectional"))
      (node (ref "U$30") (pin "2") (pinfunction "OUTG_2") (pintype "bidirectional"))
      (node (ref "U$30") (pin "3") (pinfunction "OUTB_3") (pintype "bidirectional"))
    )
    (net (code "32") (name "NEG_PAD9") (class "Default")
      (node (ref "U$33") (pin "P$1") (pinfunction "0_P$1") (pintype "bidirectional"))
      (node (ref "U$34") (pin "1") (pinfunction "OUTR_1") (pintype "bidirectional"))
      (node (ref "U$34") (pin "2") (pinfunction "OUTG_2") (pintype "bidirectional"))
      (node (ref "U$34") (pin "3") (pinfunction "OUTB_3") (pintype "bidirectional"))
    )
    (net (code "33") (name "NEG_PAD10") (class "Default")
      (node (ref "U$37") (pin "P$1") (pinfunction "0_P$1") (pintype "bidirectional"))
      (node (ref "U$38") (pin "1") (pinfunction "OUTR_1") (pintype "bidirectional"))
      (node (ref "U$38") (pin "2") (pinfunction "OUTG_2") (pintype "bidirectional"))
      (node (ref "U$38") (pin "3") (pinfunction "OUTB_3") (pintype "bidirectional"))
    )
    (net (code "34") (name "NEG_PAD11") (class "Default")
      (node (ref "U$41") (pin "P$1") (pinfunction "0_P$1") (pintype "bidirectional"))
      (node (ref "U$42") (pin "1") (pinfunction "OUTR_1") (pintype "bidirectional"))
      (node (ref "U$42") (pin "2") (pinfunction "OUTG_2") (pintype "bidirectional"))
      (node (ref "U$42") (pin "3") (pinfunction "OUTB_3") (pintype "bidirectional"))
    )
    (net (code "35") (name "NEG_PAD12") (class "Default")
      (node (ref "U$45") (pin "P$1") (pinfunction "0_P$1") (pintype "bidirectional"))
      (node (ref "U$46") (pin "1") (pinfunction "OUTR_1") (pintype "bidirectional"))
      (node (ref "U$46") (pin "2") (pinfunction "OUTG_2") (pintype "bidirectional"))
      (node (ref "U$46") (pin "3") (pinfunction "OUTB_3") (pintype "bidirectional"))
    )
    (net (code "36") (name "NEG_PAD13") (class "Default")
      (node (ref "U$49") (pin "P$1") (pinfunction "0_P$1") (pintype "bidirectional"))
      (node (ref "U$50") (pin "1") (pinfunction "OUTR_1") (pintype "bidirectional"))
      (node (ref "U$50") (pin "2") (pinfunction "OUTG_2") (pintype "bidirectional"))
      (node (ref "U$50") (pin "3") (pinfunction "OUTB_3") (pintype "bidirectional"))
    )
    (net (code "37") (name "NEG_PAD14") (class "Default")
      (node (ref "U$53") (pin "P$1") (pinfunction "0_P$1") (pintype "bidirectional"))
      (node (ref "U$54") (pin "1") (pinfunction "OUTR_1") (pintype "bidirectional"))
      (node (ref "U$54") (pin "2") (pinfunction "OUTG_2") (pintype "bidirectional"))
      (node (ref "U$54") (pin "3") (pinfunction "OUTB_3") (pintype "bidirectional"))
    )
    (net (code "38") (name "NEG_PAD15") (class "Default")
      (node (ref "U$57") (pin "P$1") (pinfunction "0_P$1") (pintype "bidirectional"))
      (node (ref "U$58") (pin "1") (pinfunction "OUTR_1") (pintype "bidirectional"))
      (node (ref "U$58") (pin "2") (pinfunction "OUTG_2") (pintype "bidirectional"))
      (node (ref "U$58") (pin "3") (pinfunction "OUTB_3") (pintype "bidirectional"))
    )
    (net (code "39") (name "NEG_PAD16") (class "Default")
      (node (ref "U$61") (pin "P$1") (pinfunction "0_P$1") (pintype "bidirectional"))
      (node (ref "U$62") (pin "1") (pinfunction "OUTR_1") (pintype "bidirectional"))
      (node (ref "U$62") (pin "2") (pinfunction "OUTG_2") (pintype "bidirectional"))
      (node (ref "U$62") (pin "3") (pinfunction "OUTB_3") (pintype "bidirectional"))
    )
    (net (code "40") (name "NEG_PAD17") (class "Default")
      (node (ref "U$65") (pin "P$1") (pinfunction "0_P$1") (pintype "bidirectional"))
      (node (ref "U$66") (pin "1") (pinfunction "OUTR_1") (pintype "bidirectional"))
      (node (ref "U$66") (pin "2") (pinfunction "OUTG_2") (pintype "bidirectional"))
      (node (ref "U$66") (pin "3") (pinfunction "OUTB_3") (pintype "bidirectional"))
    )
    (net (code "41") (name "NEG_PAD18") (class "Default")
      (node (ref "U$69") (pin "P$1") (pinfunction "0_P$1") (pintype "bidirectional"))
      (node (ref "U$70") (pin "1") (pinfunction "OUTR_1") (pintype "bidirectional"))
      (node (ref "U$70") (pin "2") (pinfunction "OUTG_2") (pintype "bidirectional"))
      (node (ref "U$70") (pin "3") (pinfunction "OUTB_3") (pintype "bidirectional"))
    )
    (net (code "42") (name "NEG_PAD19") (class "Default")
      (node (ref "U$73") (pin "P$1") (pinfunction "0_P$1") (pintype "bidirectional"))
      (node (ref "U$74") (pin "1") (pinfunction "OUTR_1") (pintype "bidirectional"))
      (node (ref "U$74") (pin "2") (pinfunction "OUTG_2") (pintype "bidirectional"))
      (node (ref "U$74") (pin "3") (pinfunction "OUTB_3") (pintype "bidirectional"))
    )
    (net (code "43") (name "NEG_PAD20") (class "Default")
      (node (ref "U$77") (pin "P$1") (pinfunction "0_P$1") (pintype "bidirectional"))
      (node (ref "U$78") (pin "1") (pinfunction "OUTR_1") (pintype "bidirectional"))
      (node (ref "U$78") (pin "2") (pinfunction "OUTG_2") (pintype "bidirectional"))
      (node (ref "U$78") (pin "3") (pinfunction "OUTB_3") (pintype "bidirectional"))
    )
    (net (code "44") (name "Net-(U$2-DIN)") (class "Default")
      (node (ref "R4") (pin "1") (pinfunction "1_1") (pintype "passive"))
      (node (ref "U$2") (pin "5") (pinfunction "DIN_5") (pintype "bidirectional"))
    )
    (net (code "45") (name "Net-(U$2-DO)") (class "Default")
      (node (ref "R5") (pin "2") (pinfunction "2_2") (pintype "passive"))
      (node (ref "U$2") (pin "4") (pinfunction "DO_4") (pintype "bidirectional"))
    )
    (net (code "46") (name "Net-(U$2-VDD)") (class "Default")
      (node (ref "R6") (pin "1") (pinfunction "1_1") (pintype "passive"))
      (node (ref "U$2") (pin "8") (pinfunction "VDD_8") (pintype "bidirectional"))
    )
    (net (code "47") (name "Net-(U$6-DIN)") (class "Default")
      (node (ref "R1") (pin "1") (pinfunction "1_1") (pintype "passive"))
      (node (ref "U$6") (pin "5") (pinfunction "DIN_5") (pintype "bidirectional"))
    )
    (net (code "48") (name "Net-(U$6-DO)") (class "Default")
      (node (ref "R2") (pin "2") (pinfunction "2_2") (pintype "passive"))
      (node (ref "U$6") (pin "4") (pinfunction "DO_4") (pintype "bidirectional"))
    )
    (net (code "49") (name "Net-(U$6-VDD)") (class "Default")
      (node (ref "R3") (pin "1") (pinfunction "1_1") (pintype "passive"))
      (node (ref "U$6") (pin "8") (pinfunction "VDD_8") (pintype "bidirectional"))
    )
    (net (code "50") (name "Net-(U$10-DIN)") (class "Default")
      (node (ref "R7") (pin "1") (pinfunction "1_1") (pintype "passive"))
      (node (ref "U$10") (pin "5") (pinfunction "DIN_5") (pintype "bidirectional"))
    )
    (net (code "51") (name "Net-(U$10-DO)") (class "Default")
      (node (ref "R8") (pin "2") (pinfunction "2_2") (pintype "passive"))
      (node (ref "U$10") (pin "4") (pinfunction "DO_4") (pintype "bidirectional"))
    )
    (net (code "52") (name "Net-(U$10-VDD)") (class "Default")
      (node (ref "R9") (pin "1") (pinfunction "1_1") (pintype "passive"))
      (node (ref "U$10") (pin "8") (pinfunction "VDD_8") (pintype "bidirectional"))
    )
    (net (code "53") (name "Net-(U$14-DIN)") (class "Default")
      (node (ref "R10") (pin "1") (pinfunction "1_1") (pintype "passive"))
      (node (ref "U$14") (pin "5") (pinfunction "DIN_5") (pintype "bidirectional"))
    )
    (net (code "54") (name "Net-(U$14-DO)") (class "Default")
      (node (ref "R11") (pin "2") (pinfunction "2_2") (pintype "passive"))
      (node (ref "U$14") (pin "4") (pinfunction "DO_4") (pintype "bidirectional"))
    )
    (net (code "55") (name "Net-(U$14-VDD)") (class "Default")
      (node (ref "R12") (pin "1") (pinfunction "1_1") (pintype "passive"))
      (node (ref "U$14") (pin "8") (pinfunction "VDD_8") (pintype "bidirectional"))
    )
    (net (code "56") (name "Net-(U$18-DIN)") (class "Default")
      (node (ref "R13") (pin "1") (pinfunction "1_1") (pintype "passive"))
      (node (ref "U$18") (pin "5") (pinfunction "DIN_5") (pintype "bidirectional"))
    )
    (net (code "57") (name "Net-(U$18-DO)") (class "Default")
      (node (ref "R14") (pin "2") (pinfunction "2_2") (pintype "passive"))
      (node (ref "U$18") (pin "4") (pinfunction "DO_4") (pintype "bidirectional"))
    )
    (net (code "58") (name "Net-(U$18-VDD)") (class "Default")
      (node (ref "R15") (pin "1") (pinfunction "1_1") (pintype "passive"))
      (node (ref "U$18") (pin "8") (pinfunction "VDD_8") (pintype "bidirectional"))
    )
    (net (code "59") (name "Net-(U$22-DIN)") (class "Default")
      (node (ref "R16") (pin "1") (pinfunction "1_1") (pintype "passive"))
      (node (ref "U$22") (pin "5") (pinfunction "DIN_5") (pintype "bidirectional"))
    )
    (net (code "60") (name "Net-(U$22-DO)") (class "Default")
      (node (ref "R17") (pin "2") (pinfunction "2_2") (pintype "passive"))
      (node (ref "U$22") (pin "4") (pinfunction "DO_4") (pintype "bidirectional"))
    )
    (net (code "61") (name "Net-(U$22-VDD)") (class "Default")
      (node (ref "R18") (pin "1") (pinfunction "1_1") (pintype "passive"))
      (node (ref "U$22") (pin "8") (pinfunction "VDD_8") (pintype "bidirectional"))
    )
    (net (code "62") (name "Net-(U$26-DIN)") (class "Default")
      (node (ref "R19") (pin "1") (pinfunction "1_1") (pintype "passive"))
      (node (ref "U$26") (pin "5") (pinfunction "DIN_5") (pintype "bidirectional"))
    )
    (net (code "63") (name "Net-(U$26-DO)") (class "Default")
      (node (ref "R20") (pin "2") (pinfunction "2_2") (pintype "passive"))
      (node (ref "U$26") (pin "4") (pinfunction "DO_4") (pintype "bidirectional"))
    )
    (net (code "64") (name "Net-(U$26-VDD)") (class "Default")
      (node (ref "R21") (pin "1") (pinfunction "1_1") (pintype "passive"))
      (node (ref "U$26") (pin "8") (pinfunction "VDD_8") (pintype "bidirectional"))
    )
    (net (code "65") (name "Net-(U$30-DIN)") (class "Default")
      (node (ref "R22") (pin "1") (pinfunction "1_1") (pintype "passive"))
      (node (ref "U$30") (pin "5") (pinfunction "DIN_5") (pintype "bidirectional"))
    )
    (net (code "66") (name "Net-(U$30-DO)") (class "Default")
      (node (ref "R23") (pin "2") (pinfunction "2_2") (pintype "passive"))
      (node (ref "U$30") (pin "4") (pinfunction "DO_4") (pintype "bidirectional"))
    )
    (net (code "67") (name "Net-(U$30-VDD)") (class "Default")
      (node (ref "R24") (pin "1") (pinfunction "1_1") (pintype "passive"))
      (node (ref "U$30") (pin "8") (pinfunction "VDD_8") (pintype "bidirectional"))
    )
    (net (code "68") (name "Net-(U$34-DIN)") (class "Default")
      (node (ref "R25") (pin "1") (pinfunction "1_1") (pintype "passive"))
      (node (ref "U$34") (pin "5") (pinfunction "DIN_5") (pintype "bidirectional"))
    )
    (net (code "69") (name "Net-(U$34-DO)") (class "Default")
      (node (ref "R26") (pin "2") (pinfunction "2_2") (pintype "passive"))
      (node (ref "U$34") (pin "4") (pinfunction "DO_4") (pintype "bidirectional"))
    )
    (net (code "70") (name "Net-(U$34-VDD)") (class "Default")
      (node (ref "R27") (pin "1") (pinfunction "1_1") (pintype "passive"))
      (node (ref "U$34") (pin "8") (pinfunction "VDD_8") (pintype "bidirectional"))
    )
    (net (code "71") (name "Net-(U$38-DIN)") (class "Default")
      (node (ref "R28") (pin "1") (pinfunction "1_1") (pintype "passive"))
      (node (ref "U$38") (pin "5") (pinfunction "DIN_5") (pintype "bidirectional"))
    )
    (net (code "72") (name "Net-(U$38-DO)") (class "Default")
      (node (ref "R29") (pin "2") (pinfunction "2_2") (pintype "passive"))
      (node (ref "U$38") (pin "4") (pinfunction "DO_4") (pintype "bidirectional"))
    )
    (net (code "73") (name "Net-(U$38-VDD)") (class "Default")
      (node (ref "R30") (pin "1") (pinfunction "1_1") (pintype "passive"))
      (node (ref "U$38") (pin "8") (pinfunction "VDD_8") (pintype "bidirectional"))
    )
    (net (code "74") (name "Net-(U$42-DIN)") (class "Default")
      (node (ref "R31") (pin "1") (pinfunction "1_1") (pintype "passive"))
      (node (ref "U$42") (pin "5") (pinfunction "DIN_5") (pintype "bidirectional"))
    )
    (net (code "75") (name "Net-(U$42-DO)") (class "Default")
      (node (ref "R32") (pin "2") (pinfunction "2_2") (pintype "passive"))
      (node (ref "U$42") (pin "4") (pinfunction "DO_4") (pintype "bidirectional"))
    )
    (net (code "76") (name "Net-(U$42-VDD)") (class "Default")
      (node (ref "R33") (pin "1") (pinfunction "1_1") (pintype "passive"))
      (node (ref "U$42") (pin "8") (pinfunction "VDD_8") (pintype "bidirectional"))
    )
    (net (code "77") (name "Net-(U$46-DIN)") (class "Default")
      (node (ref "R34") (pin "1") (pinfunction "1_1") (pintype "passive"))
      (node (ref "U$46") (pin "5") (pinfunction "DIN_5") (pintype "bidirectional"))
    )
    (net (code "78") (name "Net-(U$46-DO)") (class "Default")
      (node (ref "R35") (pin "2") (pinfunction "2_2") (pintype "passive"))
      (node (ref "U$46") (pin "4") (pinfunction "DO_4") (pintype "bidirectional"))
    )
    (net (code "79") (name "Net-(U$46-VDD)") (class "Default")
      (node (ref "R36") (pin "1") (pinfunction "1_1") (pintype "passive"))
      (node (ref "U$46") (pin "8") (pinfunction "VDD_8") (pintype "bidirectional"))
    )
    (net (code "80") (name "Net-(U$50-DIN)") (class "Default")
      (node (ref "R37") (pin "1") (pinfunction "1_1") (pintype "passive"))
      (node (ref "U$50") (pin "5") (pinfunction "DIN_5") (pintype "bidirectional"))
    )
    (net (code "81") (name "Net-(U$50-DO)") (class "Default")
      (node (ref "R38") (pin "2") (pinfunction "2_2") (pintype "passive"))
      (node (ref "U$50") (pin "4") (pinfunction "DO_4") (pintype "bidirectional"))
    )
    (net (code "82") (name "Net-(U$50-VDD)") (class "Default")
      (node (ref "R39") (pin "1") (pinfunction "1_1") (pintype "passive"))
      (node (ref "U$50") (pin "8") (pinfunction "VDD_8") (pintype "bidirectional"))
    )
    (net (code "83") (name "Net-(U$54-DIN)") (class "Default")
      (node (ref "R40") (pin "1") (pinfunction "1_1") (pintype "passive"))
      (node (ref "U$54") (pin "5") (pinfunction "DIN_5") (pintype "bidirectional"))
    )
    (net (code "84") (name "Net-(U$54-DO)") (class "Default")
      (node (ref "R41") (pin "2") (pinfunction "2_2") (pintype "passive"))
      (node (ref "U$54") (pin "4") (pinfunction "DO_4") (pintype "bidirectional"))
    )
    (net (code "85") (name "Net-(U$54-VDD)") (class "Default")
      (node (ref "R42") (pin "1") (pinfunction "1_1") (pintype "passive"))
      (node (ref "U$54") (pin "8") (pinfunction "VDD_8") (pintype "bidirectional"))
    )
    (net (code "86") (name "Net-(U$58-DIN)") (class "Default")
      (node (ref "R43") (pin "1") (pinfunction "1_1") (pintype "passive"))
      (node (ref "U$58") (pin "5") (pinfunction "DIN_5") (pintype "bidirectional"))
    )
    (net (code "87") (name "Net-(U$58-DO)") (class "Default")
      (node (ref "R44") (pin "2") (pinfunction "2_2") (pintype "passive"))
      (node (ref "U$58") (pin "4") (pinfunction "DO_4") (pintype "bidirectional"))
    )
    (net (code "88") (name "Net-(U$58-VDD)") (class "Default")
      (node (ref "R45") (pin "1") (pinfunction "1_1") (pintype "passive"))
      (node (ref "U$58") (pin "8") (pinfunction "VDD_8") (pintype "bidirectional"))
    )
    (net (code "89") (name "Net-(U$62-DIN)") (class "Default")
      (node (ref "R46") (pin "1") (pinfunction "1_1") (pintype "passive"))
      (node (ref "U$62") (pin "5") (pinfunction "DIN_5") (pintype "bidirectional"))
    )
    (net (code "90") (name "Net-(U$62-DO)") (class "Default")
      (node (ref "R47") (pin "2") (pinfunction "2_2") (pintype "passive"))
      (node (ref "U$62") (pin "4") (pinfunction "DO_4") (pintype "bidirectional"))
    )
    (net (code "91") (name "Net-(U$62-VDD)") (class "Default")
      (node (ref "R48") (pin "1") (pinfunction "1_1") (pintype "passive"))
      (node (ref "U$62") (pin "8") (pinfunction "VDD_8") (pintype "bidirectional"))
    )
    (net (code "92") (name "Net-(U$66-DIN)") (class "Default")
      (node (ref "R49") (pin "1") (pinfunction "1_1") (pintype "passive"))
      (node (ref "U$66") (pin "5") (pinfunction "DIN_5") (pintype "bidirectional"))
    )
    (net (code "93") (name "Net-(U$66-DO)") (class "Default")
      (node (ref "R50") (pin "2") (pinfunction "2_2") (pintype "passive"))
      (node (ref "U$66") (pin "4") (pinfunction "DO_4") (pintype "bidirectional"))
    )
    (net (code "94") (name "Net-(U$66-VDD)") (class "Default")
      (node (ref "R51") (pin "1") (pinfunction "1_1") (pintype "passive"))
      (node (ref "U$66") (pin "8") (pinfunction "VDD_8") (pintype "bidirectional"))
    )
    (net (code "95") (name "Net-(U$70-DIN)") (class "Default")
      (node (ref "R52") (pin "1") (pinfunction "1_1") (pintype "passive"))
      (node (ref "U$70") (pin "5") (pinfunction "DIN_5") (pintype "bidirectional"))
    )
    (net (code "96") (name "Net-(U$70-DO)") (class "Default")
      (node (ref "R53") (pin "2") (pinfunction "2_2") (pintype "passive"))
      (node (ref "U$70") (pin "4") (pinfunction "DO_4") (pintype "bidirectional"))
    )
    (net (code "97") (name "Net-(U$70-VDD)") (class "Default")
      (node (ref "R54") (pin "1") (pinfunction "1_1") (pintype "passive"))
      (node (ref "U$70") (pin "8") (pinfunction "VDD_8") (pintype "bidirectional"))
    )
    (net (code "98") (name "Net-(U$74-DIN)") (class "Default")
      (node (ref "R55") (pin "1") (pinfunction "1_1") (pintype "passive"))
      (node (ref "U$74") (pin "5") (pinfunction "DIN_5") (pintype "bidirectional"))
    )
    (net (code "99") (name "Net-(U$74-DO)") (class "Default")
      (node (ref "R56") (pin "2") (pinfunction "2_2") (pintype "passive"))
      (node (ref "U$74") (pin "4") (pinfunction "DO_4") (pintype "bidirectional"))
    )
    (net (code "100") (name "Net-(U$74-VDD)") (class "Default")
      (node (ref "R57") (pin "1") (pinfunction "1_1") (pintype "passive"))
      (node (ref "U$74") (pin "8") (pinfunction "VDD_8") (pintype "bidirectional"))
    )
    (net (code "101") (name "Net-(U$78-DIN)") (class "Default")
      (node (ref "R58") (pin "1") (pinfunction "1_1") (pintype "passive"))
      (node (ref "U$78") (pin "5") (pinfunction "DIN_5") (pintype "bidirectional"))
    )
    (net (code "102") (name "Net-(U$78-DO)") (class "Default")
      (node (ref "R59") (pin "2") (pinfunction "2_2") (pintype "passive"))
      (node (ref "U$78") (pin "4") (pinfunction "DO_4") (pintype "bidirectional"))
    )
    (net (code "103") (name "Net-(U$78-VDD)") (class "Default")
      (node (ref "R60") (pin "1") (pinfunction "1_1") (pintype "passive"))
      (node (ref "U$78") (pin "8") (pinfunction "VDD_8") (pintype "bidirectional"))
    )
    (net (code "104") (name "VCC") (class "Default")
      (node (ref "C1") (pin "1") (pinfunction "1_1") (pintype "passive"))
      (node (ref "C10") (pin "1") (pinfunction "1_1") (pintype "passive"))
      (node (ref "C11") (pin "1") (pinfunction "1_1") (pintype "passive"))
      (node (ref "C12") (pin "1") (pinfunction "1_1") (pintype "passive"))
      (node (ref "C13") (pin "1") (pinfunction "1_1") (pintype "passive"))
      (node (ref "C14") (pin "1") (pinfunction "1_1") (pintype "passive"))
      (node (ref "C15") (pin "1") (pinfunction "1_1") (pintype "passive"))
      (node (ref "C16") (pin "1") (pinfunction "1_1") (pintype "passive"))
      (node (ref "C17") (pin "1") (pinfunction "1_1") (pintype "passive"))
      (node (ref "C18") (pin "1") (pinfunction "1_1") (pintype "passive"))
      (node (ref "C19") (pin "1") (pinfunction "1_1") (pintype "passive"))
      (node (ref "C2") (pin "1") (pinfunction "1_1") (pintype "passive"))
      (node (ref "C20") (pin "1") (pinfunction "1_1") (pintype "passive"))
      (node (ref "C3") (pin "1") (pinfunction "1_1") (pintype "passive"))
      (node (ref "C4") (pin "1") (pinfunction "1_1") (pintype "passive"))
      (node (ref "C5") (pin "1") (pinfunction "1_1") (pintype "passive"))
      (node (ref "C6") (pin "1") (pinfunction "1_1") (pintype "passive"))
      (node (ref "C7") (pin "1") (pinfunction "1_1") (pintype "passive"))
      (node (ref "C8") (pin "1") (pinfunction "1_1") (pintype "passive"))
      (node (ref "C9") (pin "1") (pinfunction "1_1") (pintype "passive"))
      (node (ref "IN1") (pin "4") (pinfunction "VCC_4") (pintype "bidirectional"))
      (node (ref "OUT1") (pin "4") (pinfunction "VCC_4") (pintype "bidirectional"))
      (node (ref "R12") (pin "2") (pinfunction "2_2") (pintype "passive"))
      (node (ref "R15") (pin "2") (pinfunction "2_2") (pintype "passive"))
      (node (ref "R18") (pin "2") (pinfunction "2_2") (pintype "passive"))
      (node (ref "R21") (pin "2") (pinfunction "2_2") (pintype "passive"))
      (node (ref "R24") (pin "2") (pinfunction "2_2") (pintype "passive"))
      (node (ref "R27") (pin "2") (pinfunction "2_2") (pintype "passive"))
      (node (ref "R3") (pin "2") (pinfunction "2_2") (pintype "passive"))
      (node (ref "R30") (pin "2") (pinfunction "2_2") (pintype "passive"))
      (node (ref "R33") (pin "2") (pinfunction "2_2") (pintype "passive"))
      (node (ref "R36") (pin "2") (pinfunction "2_2") (pintype "passive"))
      (node (ref "R39") (pin "2") (pinfunction "2_2") (pintype "passive"))
      (node (ref "R42") (pin "2") (pinfunction "2_2") (pintype "passive"))
      (node (ref "R45") (pin "2") (pinfunction "2_2") (pintype "passive"))
      (node (ref "R48") (pin "2") (pinfunction "2_2") (pintype "passive"))
      (node (ref "R51") (pin "2") (pinfunction "2_2") (pintype "passive"))
      (node (ref "R54") (pin "2") (pinfunction "2_2") (pintype "passive"))
      (node (ref "R57") (pin "2") (pinfunction "2_2") (pintype "passive"))
      (node (ref "R6") (pin "2") (pinfunction "2_2") (pintype "passive"))
      (node (ref "R60") (pin "2") (pinfunction "2_2") (pintype "passive"))
      (node (ref "R9") (pin "2") (pinfunction "2_2") (pintype "passive"))
      (node (ref "U$1") (pin "P$2") (pinfunction "1_P$2") (pintype "bidirectional"))
      (node (ref "U$11") (pin "4") (pinfunction "VCC_4") (pintype "bidirectional"))
      (node (ref "U$12") (pin "4") (pinfunction "VCC_4") (pintype "bidirectional"))
      (node (ref "U$13") (pin "P$2") (pinfunction "1_P$2") (pintype "bidirectional"))
      (node (ref "U$15") (pin "4") (pinfunction "VCC_4") (pintype "bidirectional"))
      (node (ref "U$16") (pin "4") (pinfunction "VCC_4") (pintype "bidirectional"))
      (node (ref "U$17") (pin "P$2") (pinfunction "1_P$2") (pintype "bidirectional"))
      (node (ref "U$19") (pin "4") (pinfunction "VCC_4") (pintype "bidirectional"))
      (node (ref "U$20") (pin "4") (pinfunction "VCC_4") (pintype "bidirectional"))
      (node (ref "U$21") (pin "P$2") (pinfunction "1_P$2") (pintype "bidirectional"))
      (node (ref "U$23") (pin "4") (pinfunction "VCC_4") (pintype "bidirectional"))
      (node (ref "U$24") (pin "4") (pinfunction "VCC_4") (pintype "bidirectional"))
      (node (ref "U$25") (pin "P$2") (pinfunction "1_P$2") (pintype "bidirectional"))
      (node (ref "U$27") (pin "4") (pinfunction "VCC_4") (pintype "bidirectional"))
      (node (ref "U$28") (pin "4") (pinfunction "VCC_4") (pintype "bidirectional"))
      (node (ref "U$29") (pin "P$2") (pinfunction "1_P$2") (pintype "bidirectional"))
      (node (ref "U$31") (pin "4") (pinfunction "VCC_4") (pintype "bidirectional"))
      (node (ref "U$32") (pin "4") (pinfunction "VCC_4") (pintype "bidirectional"))
      (node (ref "U$33") (pin "P$2") (pinfunction "1_P$2") (pintype "bidirectional"))
      (node (ref "U$35") (pin "4") (pinfunction "VCC_4") (pintype "bidirectional"))
      (node (ref "U$36") (pin "4") (pinfunction "VCC_4") (pintype "bidirectional"))
      (node (ref "U$37") (pin "P$2") (pinfunction "1_P$2") (pintype "bidirectional"))
      (node (ref "U$39") (pin "4") (pinfunction "VCC_4") (pintype "bidirectional"))
      (node (ref "U$40") (pin "4") (pinfunction "VCC_4") (pintype "bidirectional"))
      (node (ref "U$41") (pin "P$2") (pinfunction "1_P$2") (pintype "bidirectional"))
      (node (ref "U$43") (pin "4") (pinfunction "VCC_4") (pintype "bidirectional"))
      (node (ref "U$44") (pin "4") (pinfunction "VCC_4") (pintype "bidirectional"))
      (node (ref "U$45") (pin "P$2") (pinfunction "1_P$2") (pintype "bidirectional"))
      (node (ref "U$47") (pin "4") (pinfunction "VCC_4") (pintype "bidirectional"))
      (node (ref "U$48") (pin "4") (pinfunction "VCC_4") (pintype "bidirectional"))
      (node (ref "U$49") (pin "P$2") (pinfunction "1_P$2") (pintype "bidirectional"))
      (node (ref "U$5") (pin "P$2") (pinfunction "1_P$2") (pintype "bidirectional"))
      (node (ref "U$51") (pin "4") (pinfunction "VCC_4") (pintype "bidirectional"))
      (node (ref "U$52") (pin "4") (pinfunction "VCC_4") (pintype "bidirectional"))
      (node (ref "U$53") (pin "P$2") (pinfunction "1_P$2") (pintype "bidirectional"))
      (node (ref "U$55") (pin "4") (pinfunction "VCC_4") (pintype "bidirectional"))
      (node (ref "U$56") (pin "4") (pinfunction "VCC_4") (pintype "bidirectional"))
      (node (ref "U$57") (pin "P$2") (pinfunction "1_P$2") (pintype "bidirectional"))
      (node (ref "U$59") (pin "4") (pinfunction "VCC_4") (pintype "bidirectional"))
      (node (ref "U$60") (pin "4") (pinfunction "VCC_4") (pintype "bidirectional"))
      (node (ref "U$61") (pin "P$2") (pinfunction "1_P$2") (pintype "bidirectional"))
      (node (ref "U$63") (pin "4") (pinfunction "VCC_4") (pintype "bidirectional"))
      (node (ref "U$64") (pin "4") (pinfunction "VCC_4") (pintype "bidirectional"))
      (node (ref "U$65") (pin "P$2") (pinfunction "1_P$2") (pintype "bidirectional"))
      (node (ref "U$67") (pin "4") (pinfunction "VCC_4") (pintype "bidirectional"))
      (node (ref "U$68") (pin "4") (pinfunction "VCC_4") (pintype "bidirectional"))
      (node (ref "U$69") (pin "P$2") (pinfunction "1_P$2") (pintype "bidirectional"))
      (node (ref "U$7") (pin "4") (pinfunction "VCC_4") (pintype "bidirectional"))
      (node (ref "U$71") (pin "4") (pinfunction "VCC_4") (pintype "bidirectional"))
      (node (ref "U$72") (pin "4") (pinfunction "VCC_4") (pintype "bidirectional"))
      (node (ref "U$73") (pin "P$2") (pinfunction "1_P$2") (pintype "bidirectional"))
      (node (ref "U$75") (pin "4") (pinfunction "VCC_4") (pintype "bidirectional"))
      (node (ref "U$76") (pin "4") (pinfunction "VCC_4") (pintype "bidirectional"))
      (node (ref "U$77") (pin "P$2") (pinfunction "1_P$2") (pintype "bidirectional"))
      (node (ref "U$79") (pin "4") (pinfunction "VCC_4") (pintype "bidirectional"))
      (node (ref "U$8") (pin "4") (pinfunction "VCC_4") (pintype "bidirectional"))
      (node (ref "U$80") (pin "4") (pinfunction "VCC_4") (pintype "bidirectional"))
      (node (ref "U$9") (pin "P$2") (pinfunction "1_P$2") (pintype "bidirectional"))
    )
  )
)
